# ProPrj_LogicCard.net
KiCad netlist of a schematic drawn in EasyEDA Pro
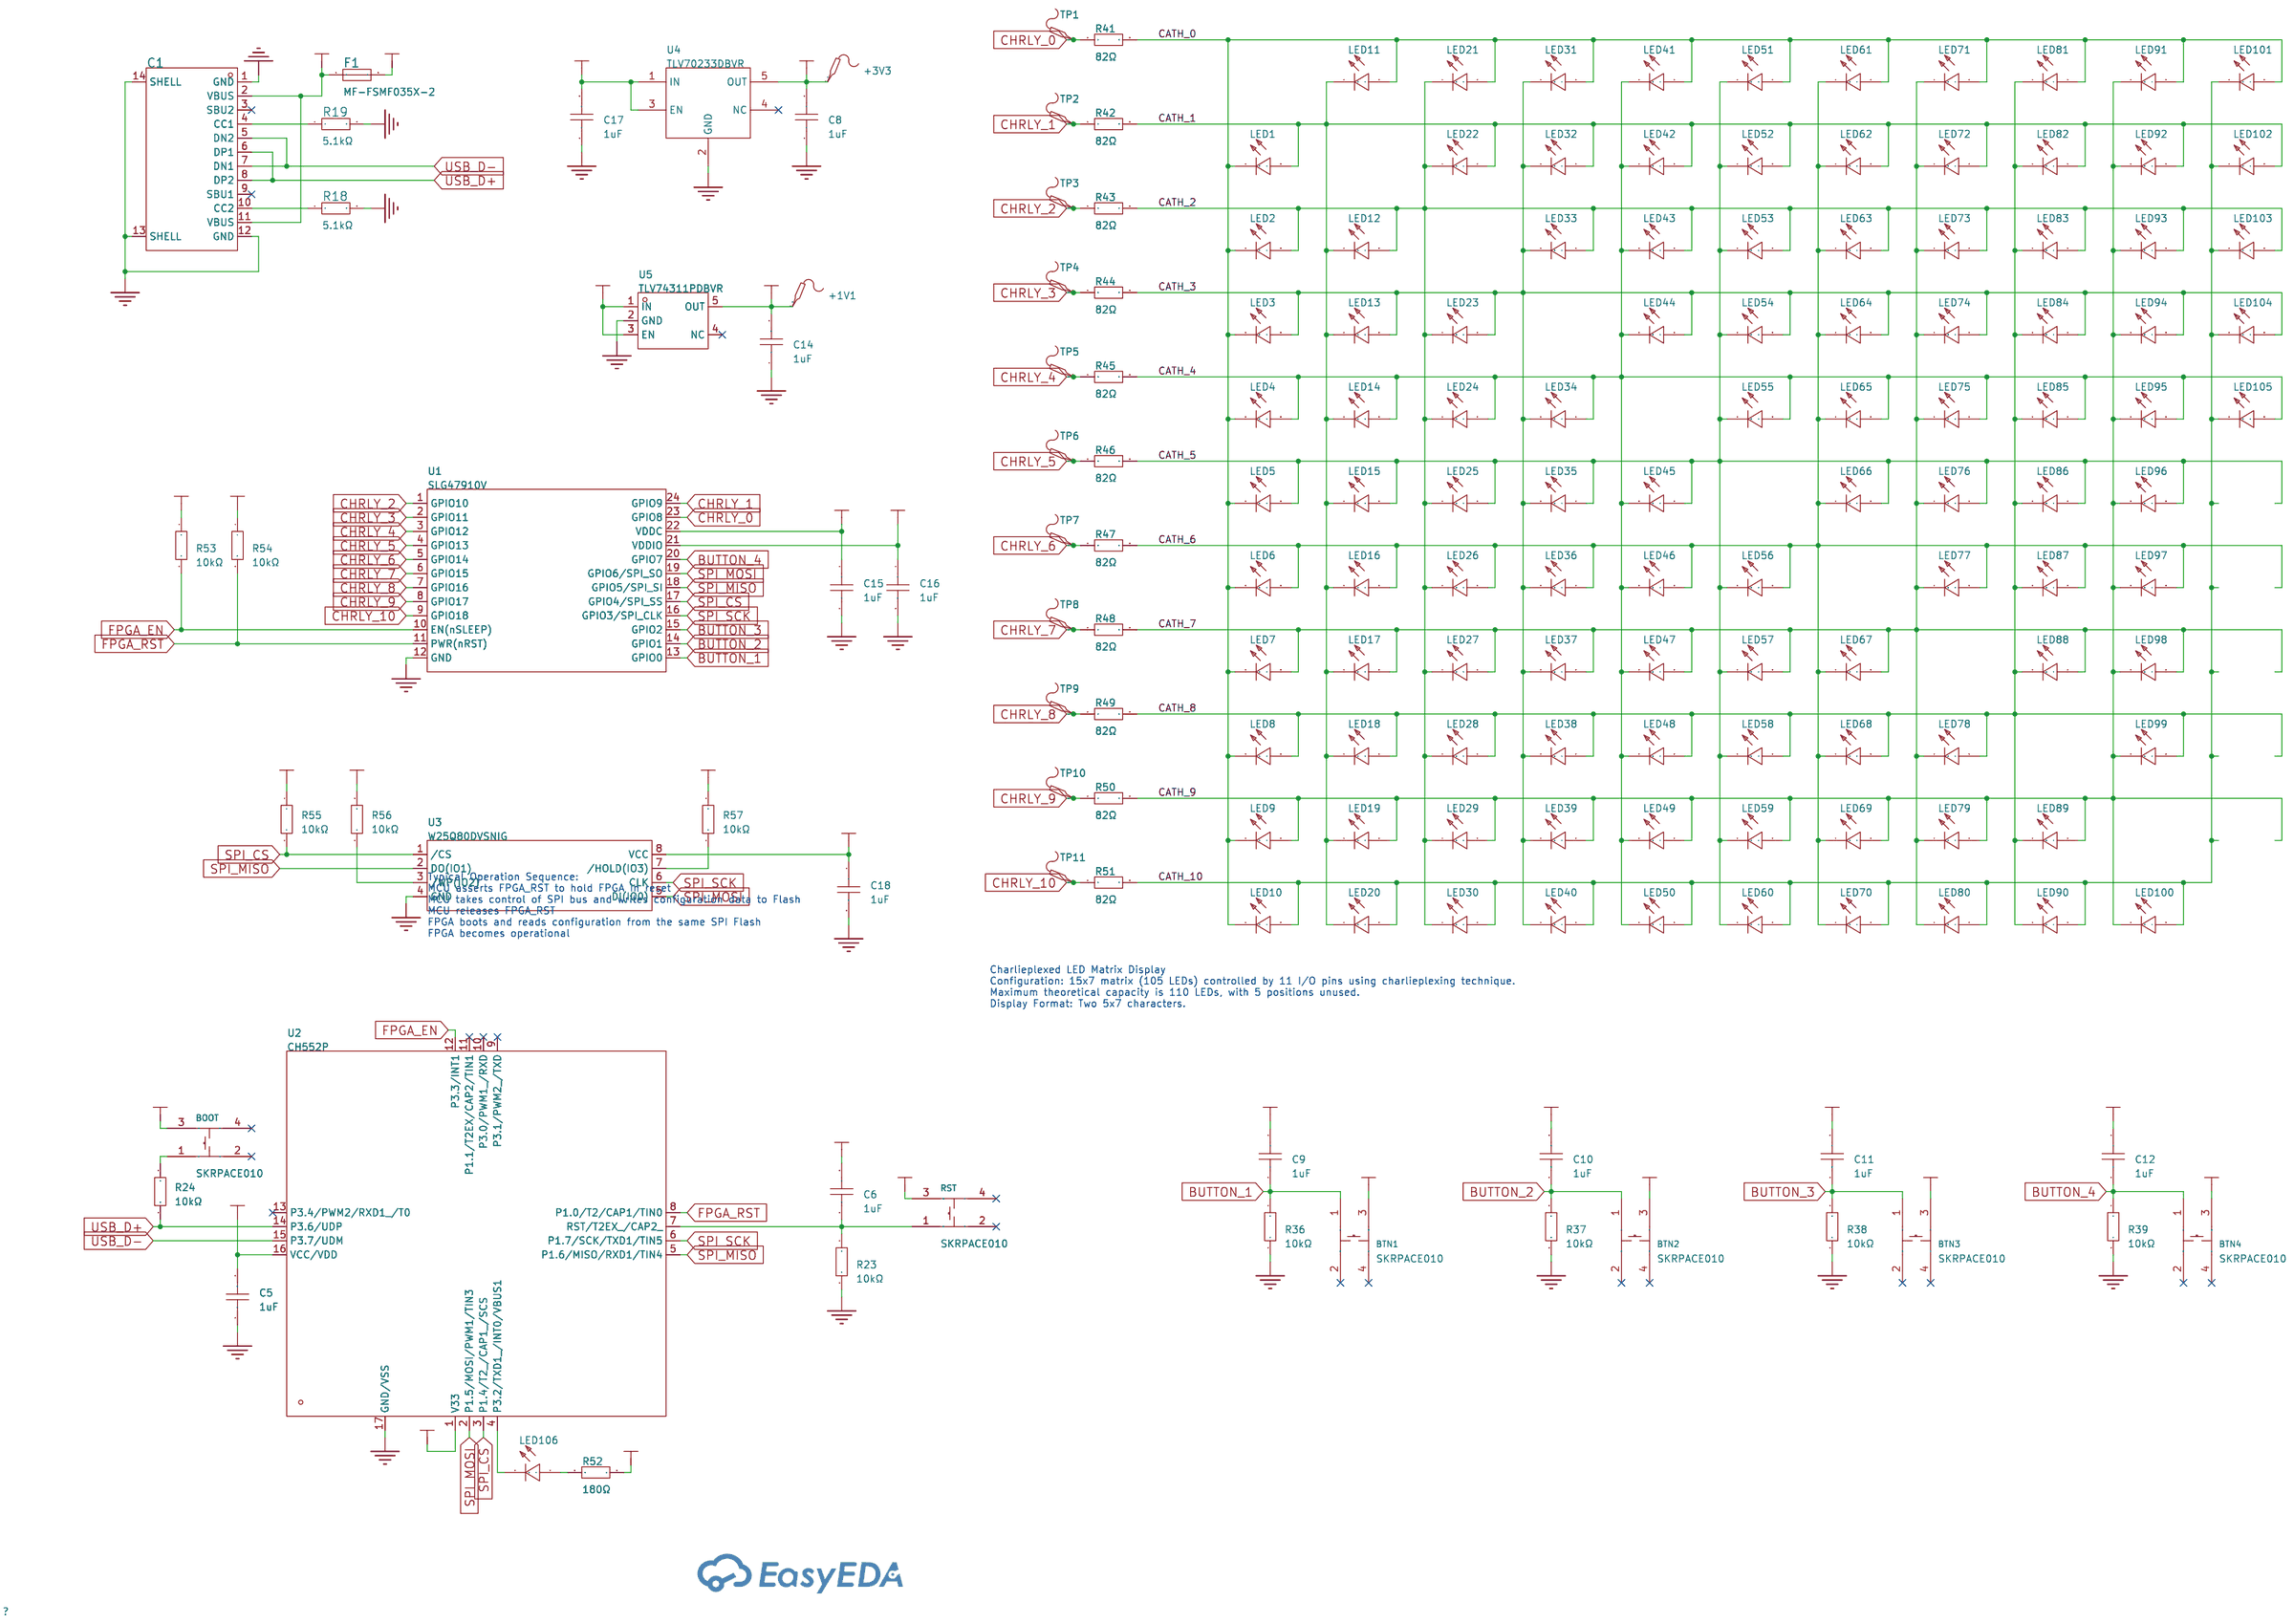
[diagram p0: schematic sheet]

(export (version "E")
  (design (tool "Eeschema 10.0.6"))
  (components
    (comp (ref "+1V1")
      (value "~")
      (footprint "easyedapro:Test-Point-0.5mm")
      (description "Test Point 测试点")
      (libsource (lib "easyedapro") (part "Test-Point"))
    )
    (comp (ref "+3V3")
      (value "~")
      (footprint "easyedapro:Test-Point-0.5mm")
      (description "Test Point 测试点")
      (libsource (lib "easyedapro") (part "Test-Point"))
    )
    (comp (ref "BOOT")
      (value "SKRPACE010")
      (footprint "easyedapro:KEY-SMD_4P-L4.2-W3.2-P2.20-LS4.6")
      (fields (field (name "Manufacturer") "ALPSALPINE(阿尔卑斯阿尔派)"))
      (libsource (lib "easyedapro") (part "SKRPACE010"))
    )
    (comp (ref "BTN1")
      (value "SKRPACE010")
      (footprint "easyedapro:KEY-SMD_4P-L4.2-W3.2-P2.20-LS4.6")
      (fields (field (name "Manufacturer") "ALPSALPINE(阿尔卑斯阿尔派)"))
      (libsource (lib "easyedapro") (part "SKRPACE010"))
    )
    (comp (ref "BTN2")
      (value "SKRPACE010")
      (footprint "easyedapro:KEY-SMD_4P-L4.2-W3.2-P2.20-LS4.6")
      (fields (field (name "Manufacturer") "ALPSALPINE(阿尔卑斯阿尔派)"))
      (libsource (lib "easyedapro") (part "SKRPACE010"))
    )
    (comp (ref "BTN3")
      (value "SKRPACE010")
      (footprint "easyedapro:KEY-SMD_4P-L4.2-W3.2-P2.20-LS4.6")
      (fields (field (name "Manufacturer") "ALPSALPINE(阿尔卑斯阿尔派)"))
      (libsource (lib "easyedapro") (part "SKRPACE010"))
    )
    (comp (ref "BTN4")
      (value "SKRPACE010")
      (footprint "easyedapro:KEY-SMD_4P-L4.2-W3.2-P2.20-LS4.6")
      (fields (field (name "Manufacturer") "ALPSALPINE(阿尔卑斯阿尔派)"))
      (libsource (lib "easyedapro") (part "SKRPACE010"))
    )
    (comp (ref "C1")
      (value "TYPE-C 16PIN 2MD(073)")
      (footprint "easyedapro:USB-C-SMD_TYPE-C-6PIN-2MD-073")
      (fields (field (name "Manufacturer") "SHOU HAN(首韩)"))
      (libsource (lib "easyedapro") (part "TYPE-C 16PIN 2MD(073)"))
    )
    (comp (ref "C5")
      (value "1uF")
      (footprint "easyedapro:C0402")
      (fields
        (field (name "Manufacturer Part") "GRM155Z71A105KE01D")
        (field (name "Manufacturer") "muRata(村田)")
      )
      (libsource (lib "easyedapro") (part "GRM155Z71A105KE01D"))
    )
    (comp (ref "C6")
      (value "1uF")
      (footprint "easyedapro:C0402")
      (fields
        (field (name "Manufacturer Part") "GRM155Z71A105KE01D")
        (field (name "Manufacturer") "muRata(村田)")
      )
      (libsource (lib "easyedapro") (part "GRM155Z71A105KE01D"))
    )
    (comp (ref "C8")
      (value "1uF")
      (footprint "easyedapro:C0402")
      (fields
        (field (name "Manufacturer Part") "GRM155Z71A105KE01D")
        (field (name "Manufacturer") "muRata(村田)")
      )
      (libsource (lib "easyedapro") (part "GRM155Z71A105KE01D"))
    )
    (comp (ref "C9")
      (value "1uF")
      (footprint "easyedapro:C0402")
      (fields
        (field (name "Manufacturer Part") "GRM155Z71A105KE01D")
        (field (name "Manufacturer") "muRata(村田)")
      )
      (libsource (lib "easyedapro") (part "GRM155Z71A105KE01D"))
    )
    (comp (ref "C10")
      (value "1uF")
      (footprint "easyedapro:C0402")
      (fields
        (field (name "Manufacturer Part") "GRM155Z71A105KE01D")
        (field (name "Manufacturer") "muRata(村田)")
      )
      (libsource (lib "easyedapro") (part "GRM155Z71A105KE01D"))
    )
    (comp (ref "C11")
      (value "1uF")
      (footprint "easyedapro:C0402")
      (fields
        (field (name "Manufacturer Part") "GRM155Z71A105KE01D")
        (field (name "Manufacturer") "muRata(村田)")
      )
      (libsource (lib "easyedapro") (part "GRM155Z71A105KE01D"))
    )
    (comp (ref "C12")
      (value "1uF")
      (footprint "easyedapro:C0402")
      (fields
        (field (name "Manufacturer Part") "GRM155Z71A105KE01D")
        (field (name "Manufacturer") "muRata(村田)")
      )
      (libsource (lib "easyedapro") (part "GRM155Z71A105KE01D"))
    )
    (comp (ref "C14")
      (value "1uF")
      (footprint "easyedapro:C0402")
      (fields
        (field (name "Manufacturer Part") "GRM155Z71A105KE01D")
        (field (name "Manufacturer") "muRata(村田)")
      )
      (libsource (lib "easyedapro") (part "GRM155Z71A105KE01D"))
    )
    (comp (ref "C15")
      (value "1uF")
      (footprint "easyedapro:C0402")
      (fields
        (field (name "Manufacturer Part") "GRM155Z71A105KE01D")
        (field (name "Manufacturer") "muRata(村田)")
      )
      (libsource (lib "easyedapro") (part "GRM155Z71A105KE01D"))
    )
    (comp (ref "C16")
      (value "1uF")
      (footprint "easyedapro:C0402")
      (fields
        (field (name "Manufacturer Part") "GRM155Z71A105KE01D")
        (field (name "Manufacturer") "muRata(村田)")
      )
      (libsource (lib "easyedapro") (part "GRM155Z71A105KE01D"))
    )
    (comp (ref "C17")
      (value "1uF")
      (footprint "easyedapro:C0402")
      (fields
        (field (name "Manufacturer Part") "GRM155Z71A105KE01D")
        (field (name "Manufacturer") "muRata(村田)")
      )
      (libsource (lib "easyedapro") (part "GRM155Z71A105KE01D"))
    )
    (comp (ref "C18")
      (value "1uF")
      (footprint "easyedapro:C0402")
      (fields
        (field (name "Manufacturer Part") "GRM155Z71A105KE01D")
        (field (name "Manufacturer") "muRata(村田)")
      )
      (libsource (lib "easyedapro") (part "GRM155Z71A105KE01D"))
    )
    (comp (ref "F1")
      (value "MF-FSMF035X-2")
      (footprint "easyedapro:F0603")
      (fields (field (name "Manufacturer") "BOURNS"))
      (libsource (lib "easyedapro") (part "MF-FSMF035X-2"))
    )
    (comp (ref "LED1")
      (value "19-213/Y2C-CQ2R2L/3T(CY)")
      (footprint "easyedapro:LED0603-RD-YELLOW")
      (fields (field (name "Manufacturer") "EVERLIGHT(亿光)"))
      (libsource (lib "easyedapro") (part "19-213/Y2C-CQ2R2L/3T(CY)"))
    )
    (comp (ref "LED2")
      (value "19-213/Y2C-CQ2R2L/3T(CY)")
      (footprint "easyedapro:LED0603-RD-YELLOW")
      (fields (field (name "Manufacturer") "EVERLIGHT(亿光)"))
      (libsource (lib "easyedapro") (part "19-213/Y2C-CQ2R2L/3T(CY)"))
    )
    (comp (ref "LED3")
      (value "19-213/Y2C-CQ2R2L/3T(CY)")
      (footprint "easyedapro:LED0603-RD-YELLOW")
      (fields (field (name "Manufacturer") "EVERLIGHT(亿光)"))
      (libsource (lib "easyedapro") (part "19-213/Y2C-CQ2R2L/3T(CY)"))
    )
    (comp (ref "LED4")
      (value "19-213/Y2C-CQ2R2L/3T(CY)")
      (footprint "easyedapro:LED0603-RD-YELLOW")
      (fields (field (name "Manufacturer") "EVERLIGHT(亿光)"))
      (libsource (lib "easyedapro") (part "19-213/Y2C-CQ2R2L/3T(CY)"))
    )
    (comp (ref "LED5")
      (value "19-213/Y2C-CQ2R2L/3T(CY)")
      (footprint "easyedapro:LED0603-RD-YELLOW")
      (fields (field (name "Manufacturer") "EVERLIGHT(亿光)"))
      (libsource (lib "easyedapro") (part "19-213/Y2C-CQ2R2L/3T(CY)"))
    )
    (comp (ref "LED6")
      (value "19-213/Y2C-CQ2R2L/3T(CY)")
      (footprint "easyedapro:LED0603-RD-YELLOW")
      (fields (field (name "Manufacturer") "EVERLIGHT(亿光)"))
      (libsource (lib "easyedapro") (part "19-213/Y2C-CQ2R2L/3T(CY)"))
    )
    (comp (ref "LED7")
      (value "19-213/Y2C-CQ2R2L/3T(CY)")
      (footprint "easyedapro:LED0603-RD-YELLOW")
      (fields (field (name "Manufacturer") "EVERLIGHT(亿光)"))
      (libsource (lib "easyedapro") (part "19-213/Y2C-CQ2R2L/3T(CY)"))
    )
    (comp (ref "LED8")
      (value "19-213/Y2C-CQ2R2L/3T(CY)")
      (footprint "easyedapro:LED0603-RD-YELLOW")
      (fields (field (name "Manufacturer") "EVERLIGHT(亿光)"))
      (libsource (lib "easyedapro") (part "19-213/Y2C-CQ2R2L/3T(CY)"))
    )
    (comp (ref "LED9")
      (value "19-213/Y2C-CQ2R2L/3T(CY)")
      (footprint "easyedapro:LED0603-RD-YELLOW")
      (fields (field (name "Manufacturer") "EVERLIGHT(亿光)"))
      (libsource (lib "easyedapro") (part "19-213/Y2C-CQ2R2L/3T(CY)"))
    )
    (comp (ref "LED10")
      (value "19-213/Y2C-CQ2R2L/3T(CY)")
      (footprint "easyedapro:LED0603-RD-YELLOW")
      (fields (field (name "Manufacturer") "EVERLIGHT(亿光)"))
      (libsource (lib "easyedapro") (part "19-213/Y2C-CQ2R2L/3T(CY)"))
    )
    (comp (ref "LED11")
      (value "19-213/Y2C-CQ2R2L/3T(CY)")
      (footprint "easyedapro:LED0603-RD-YELLOW")
      (fields (field (name "Manufacturer") "EVERLIGHT(亿光)"))
      (libsource (lib "easyedapro") (part "19-213/Y2C-CQ2R2L/3T(CY)"))
    )
    (comp (ref "LED12")
      (value "19-213/Y2C-CQ2R2L/3T(CY)")
      (footprint "easyedapro:LED0603-RD-YELLOW")
      (fields (field (name "Manufacturer") "EVERLIGHT(亿光)"))
      (libsource (lib "easyedapro") (part "19-213/Y2C-CQ2R2L/3T(CY)"))
    )
    (comp (ref "LED13")
      (value "19-213/Y2C-CQ2R2L/3T(CY)")
      (footprint "easyedapro:LED0603-RD-YELLOW")
      (fields (field (name "Manufacturer") "EVERLIGHT(亿光)"))
      (libsource (lib "easyedapro") (part "19-213/Y2C-CQ2R2L/3T(CY)"))
    )
    (comp (ref "LED14")
      (value "19-213/Y2C-CQ2R2L/3T(CY)")
      (footprint "easyedapro:LED0603-RD-YELLOW")
      (fields (field (name "Manufacturer") "EVERLIGHT(亿光)"))
      (libsource (lib "easyedapro") (part "19-213/Y2C-CQ2R2L/3T(CY)"))
    )
    (comp (ref "LED15")
      (value "19-213/Y2C-CQ2R2L/3T(CY)")
      (footprint "easyedapro:LED0603-RD-YELLOW")
      (fields (field (name "Manufacturer") "EVERLIGHT(亿光)"))
      (libsource (lib "easyedapro") (part "19-213/Y2C-CQ2R2L/3T(CY)"))
    )
    (comp (ref "LED16")
      (value "19-213/Y2C-CQ2R2L/3T(CY)")
      (footprint "easyedapro:LED0603-RD-YELLOW")
      (fields (field (name "Manufacturer") "EVERLIGHT(亿光)"))
      (libsource (lib "easyedapro") (part "19-213/Y2C-CQ2R2L/3T(CY)"))
    )
    (comp (ref "LED17")
      (value "19-213/Y2C-CQ2R2L/3T(CY)")
      (footprint "easyedapro:LED0603-RD-YELLOW")
      (fields (field (name "Manufacturer") "EVERLIGHT(亿光)"))
      (libsource (lib "easyedapro") (part "19-213/Y2C-CQ2R2L/3T(CY)"))
    )
    (comp (ref "LED18")
      (value "19-213/Y2C-CQ2R2L/3T(CY)")
      (footprint "easyedapro:LED0603-RD-YELLOW")
      (fields (field (name "Manufacturer") "EVERLIGHT(亿光)"))
      (libsource (lib "easyedapro") (part "19-213/Y2C-CQ2R2L/3T(CY)"))
    )
    (comp (ref "LED19")
      (value "19-213/Y2C-CQ2R2L/3T(CY)")
      (footprint "easyedapro:LED0603-RD-YELLOW")
      (fields (field (name "Manufacturer") "EVERLIGHT(亿光)"))
      (libsource (lib "easyedapro") (part "19-213/Y2C-CQ2R2L/3T(CY)"))
    )
    (comp (ref "LED20")
      (value "19-213/Y2C-CQ2R2L/3T(CY)")
      (footprint "easyedapro:LED0603-RD-YELLOW")
      (fields (field (name "Manufacturer") "EVERLIGHT(亿光)"))
      (libsource (lib "easyedapro") (part "19-213/Y2C-CQ2R2L/3T(CY)"))
    )
    (comp (ref "LED21")
      (value "19-213/Y2C-CQ2R2L/3T(CY)")
      (footprint "easyedapro:LED0603-RD-YELLOW")
      (fields (field (name "Manufacturer") "EVERLIGHT(亿光)"))
      (libsource (lib "easyedapro") (part "19-213/Y2C-CQ2R2L/3T(CY)"))
    )
    (comp (ref "LED22")
      (value "19-213/Y2C-CQ2R2L/3T(CY)")
      (footprint "easyedapro:LED0603-RD-YELLOW")
      (fields (field (name "Manufacturer") "EVERLIGHT(亿光)"))
      (libsource (lib "easyedapro") (part "19-213/Y2C-CQ2R2L/3T(CY)"))
    )
    (comp (ref "LED23")
      (value "19-213/Y2C-CQ2R2L/3T(CY)")
      (footprint "easyedapro:LED0603-RD-YELLOW")
      (fields (field (name "Manufacturer") "EVERLIGHT(亿光)"))
      (libsource (lib "easyedapro") (part "19-213/Y2C-CQ2R2L/3T(CY)"))
    )
    (comp (ref "LED24")
      (value "19-213/Y2C-CQ2R2L/3T(CY)")
      (footprint "easyedapro:LED0603-RD-YELLOW")
      (fields (field (name "Manufacturer") "EVERLIGHT(亿光)"))
      (libsource (lib "easyedapro") (part "19-213/Y2C-CQ2R2L/3T(CY)"))
    )
    (comp (ref "LED25")
      (value "19-213/Y2C-CQ2R2L/3T(CY)")
      (footprint "easyedapro:LED0603-RD-YELLOW")
      (fields (field (name "Manufacturer") "EVERLIGHT(亿光)"))
      (libsource (lib "easyedapro") (part "19-213/Y2C-CQ2R2L/3T(CY)"))
    )
    (comp (ref "LED26")
      (value "19-213/Y2C-CQ2R2L/3T(CY)")
      (footprint "easyedapro:LED0603-RD-YELLOW")
      (fields (field (name "Manufacturer") "EVERLIGHT(亿光)"))
      (libsource (lib "easyedapro") (part "19-213/Y2C-CQ2R2L/3T(CY)"))
    )
    (comp (ref "LED27")
      (value "19-213/Y2C-CQ2R2L/3T(CY)")
      (footprint "easyedapro:LED0603-RD-YELLOW")
      (fields (field (name "Manufacturer") "EVERLIGHT(亿光)"))
      (libsource (lib "easyedapro") (part "19-213/Y2C-CQ2R2L/3T(CY)"))
    )
    (comp (ref "LED28")
      (value "19-213/Y2C-CQ2R2L/3T(CY)")
      (footprint "easyedapro:LED0603-RD-YELLOW")
      (fields (field (name "Manufacturer") "EVERLIGHT(亿光)"))
      (libsource (lib "easyedapro") (part "19-213/Y2C-CQ2R2L/3T(CY)"))
    )
    (comp (ref "LED29")
      (value "19-213/Y2C-CQ2R2L/3T(CY)")
      (footprint "easyedapro:LED0603-RD-YELLOW")
      (fields (field (name "Manufacturer") "EVERLIGHT(亿光)"))
      (libsource (lib "easyedapro") (part "19-213/Y2C-CQ2R2L/3T(CY)"))
    )
    (comp (ref "LED30")
      (value "19-213/Y2C-CQ2R2L/3T(CY)")
      (footprint "easyedapro:LED0603-RD-YELLOW")
      (fields (field (name "Manufacturer") "EVERLIGHT(亿光)"))
      (libsource (lib "easyedapro") (part "19-213/Y2C-CQ2R2L/3T(CY)"))
    )
    (comp (ref "LED31")
      (value "19-213/Y2C-CQ2R2L/3T(CY)")
      (footprint "easyedapro:LED0603-RD-YELLOW")
      (fields (field (name "Manufacturer") "EVERLIGHT(亿光)"))
      (libsource (lib "easyedapro") (part "19-213/Y2C-CQ2R2L/3T(CY)"))
    )
    (comp (ref "LED32")
      (value "19-213/Y2C-CQ2R2L/3T(CY)")
      (footprint "easyedapro:LED0603-RD-YELLOW")
      (fields (field (name "Manufacturer") "EVERLIGHT(亿光)"))
      (libsource (lib "easyedapro") (part "19-213/Y2C-CQ2R2L/3T(CY)"))
    )
    (comp (ref "LED33")
      (value "19-213/Y2C-CQ2R2L/3T(CY)")
      (footprint "easyedapro:LED0603-RD-YELLOW")
      (fields (field (name "Manufacturer") "EVERLIGHT(亿光)"))
      (libsource (lib "easyedapro") (part "19-213/Y2C-CQ2R2L/3T(CY)"))
    )
    (comp (ref "LED34")
      (value "19-213/Y2C-CQ2R2L/3T(CY)")
      (footprint "easyedapro:LED0603-RD-YELLOW")
      (fields (field (name "Manufacturer") "EVERLIGHT(亿光)"))
      (libsource (lib "easyedapro") (part "19-213/Y2C-CQ2R2L/3T(CY)"))
    )
    (comp (ref "LED35")
      (value "19-213/Y2C-CQ2R2L/3T(CY)")
      (footprint "easyedapro:LED0603-RD-YELLOW")
      (fields (field (name "Manufacturer") "EVERLIGHT(亿光)"))
      (libsource (lib "easyedapro") (part "19-213/Y2C-CQ2R2L/3T(CY)"))
    )
    (comp (ref "LED36")
      (value "19-213/Y2C-CQ2R2L/3T(CY)")
      (footprint "easyedapro:LED0603-RD-YELLOW")
      (fields (field (name "Manufacturer") "EVERLIGHT(亿光)"))
      (libsource (lib "easyedapro") (part "19-213/Y2C-CQ2R2L/3T(CY)"))
    )
    (comp (ref "LED37")
      (value "19-213/Y2C-CQ2R2L/3T(CY)")
      (footprint "easyedapro:LED0603-RD-YELLOW")
      (fields (field (name "Manufacturer") "EVERLIGHT(亿光)"))
      (libsource (lib "easyedapro") (part "19-213/Y2C-CQ2R2L/3T(CY)"))
    )
    (comp (ref "LED38")
      (value "19-213/Y2C-CQ2R2L/3T(CY)")
      (footprint "easyedapro:LED0603-RD-YELLOW")
      (fields (field (name "Manufacturer") "EVERLIGHT(亿光)"))
      (libsource (lib "easyedapro") (part "19-213/Y2C-CQ2R2L/3T(CY)"))
    )
    (comp (ref "LED39")
      (value "19-213/Y2C-CQ2R2L/3T(CY)")
      (footprint "easyedapro:LED0603-RD-YELLOW")
      (fields (field (name "Manufacturer") "EVERLIGHT(亿光)"))
      (libsource (lib "easyedapro") (part "19-213/Y2C-CQ2R2L/3T(CY)"))
    )
    (comp (ref "LED40")
      (value "19-213/Y2C-CQ2R2L/3T(CY)")
      (footprint "easyedapro:LED0603-RD-YELLOW")
      (fields (field (name "Manufacturer") "EVERLIGHT(亿光)"))
      (libsource (lib "easyedapro") (part "19-213/Y2C-CQ2R2L/3T(CY)"))
    )
    (comp (ref "LED41")
      (value "19-213/Y2C-CQ2R2L/3T(CY)")
      (footprint "easyedapro:LED0603-RD-YELLOW")
      (fields (field (name "Manufacturer") "EVERLIGHT(亿光)"))
      (libsource (lib "easyedapro") (part "19-213/Y2C-CQ2R2L/3T(CY)"))
    )
    (comp (ref "LED42")
      (value "19-213/Y2C-CQ2R2L/3T(CY)")
      (footprint "easyedapro:LED0603-RD-YELLOW")
      (fields (field (name "Manufacturer") "EVERLIGHT(亿光)"))
      (libsource (lib "easyedapro") (part "19-213/Y2C-CQ2R2L/3T(CY)"))
    )
    (comp (ref "LED43")
      (value "19-213/Y2C-CQ2R2L/3T(CY)")
      (footprint "easyedapro:LED0603-RD-YELLOW")
      (fields (field (name "Manufacturer") "EVERLIGHT(亿光)"))
      (libsource (lib "easyedapro") (part "19-213/Y2C-CQ2R2L/3T(CY)"))
    )
    (comp (ref "LED44")
      (value "19-213/Y2C-CQ2R2L/3T(CY)")
      (footprint "easyedapro:LED0603-RD-YELLOW")
      (fields (field (name "Manufacturer") "EVERLIGHT(亿光)"))
      (libsource (lib "easyedapro") (part "19-213/Y2C-CQ2R2L/3T(CY)"))
    )
    (comp (ref "LED45")
      (value "19-213/Y2C-CQ2R2L/3T(CY)")
      (footprint "easyedapro:LED0603-RD-YELLOW")
      (fields (field (name "Manufacturer") "EVERLIGHT(亿光)"))
      (libsource (lib "easyedapro") (part "19-213/Y2C-CQ2R2L/3T(CY)"))
    )
    (comp (ref "LED46")
      (value "19-213/Y2C-CQ2R2L/3T(CY)")
      (footprint "easyedapro:LED0603-RD-YELLOW")
      (fields (field (name "Manufacturer") "EVERLIGHT(亿光)"))
      (libsource (lib "easyedapro") (part "19-213/Y2C-CQ2R2L/3T(CY)"))
    )
    (comp (ref "LED47")
      (value "19-213/Y2C-CQ2R2L/3T(CY)")
      (footprint "easyedapro:LED0603-RD-YELLOW")
      (fields (field (name "Manufacturer") "EVERLIGHT(亿光)"))
      (libsource (lib "easyedapro") (part "19-213/Y2C-CQ2R2L/3T(CY)"))
    )
    (comp (ref "LED48")
      (value "19-213/Y2C-CQ2R2L/3T(CY)")
      (footprint "easyedapro:LED0603-RD-YELLOW")
      (fields (field (name "Manufacturer") "EVERLIGHT(亿光)"))
      (libsource (lib "easyedapro") (part "19-213/Y2C-CQ2R2L/3T(CY)"))
    )
    (comp (ref "LED49")
      (value "19-213/Y2C-CQ2R2L/3T(CY)")
      (footprint "easyedapro:LED0603-RD-YELLOW")
      (fields (field (name "Manufacturer") "EVERLIGHT(亿光)"))
      (libsource (lib "easyedapro") (part "19-213/Y2C-CQ2R2L/3T(CY)"))
    )
    (comp (ref "LED50")
      (value "19-213/Y2C-CQ2R2L/3T(CY)")
      (footprint "easyedapro:LED0603-RD-YELLOW")
      (fields (field (name "Manufacturer") "EVERLIGHT(亿光)"))
      (libsource (lib "easyedapro") (part "19-213/Y2C-CQ2R2L/3T(CY)"))
    )
    (comp (ref "LED51")
      (value "19-213/Y2C-CQ2R2L/3T(CY)")
      (footprint "easyedapro:LED0603-RD-YELLOW")
      (fields (field (name "Manufacturer") "EVERLIGHT(亿光)"))
      (libsource (lib "easyedapro") (part "19-213/Y2C-CQ2R2L/3T(CY)"))
    )
    (comp (ref "LED52")
      (value "19-213/Y2C-CQ2R2L/3T(CY)")
      (footprint "easyedapro:LED0603-RD-YELLOW")
      (fields (field (name "Manufacturer") "EVERLIGHT(亿光)"))
      (libsource (lib "easyedapro") (part "19-213/Y2C-CQ2R2L/3T(CY)"))
    )
    (comp (ref "LED53")
      (value "19-213/Y2C-CQ2R2L/3T(CY)")
      (footprint "easyedapro:LED0603-RD-YELLOW")
      (fields (field (name "Manufacturer") "EVERLIGHT(亿光)"))
      (libsource (lib "easyedapro") (part "19-213/Y2C-CQ2R2L/3T(CY)"))
    )
    (comp (ref "LED54")
      (value "19-213/Y2C-CQ2R2L/3T(CY)")
      (footprint "easyedapro:LED0603-RD-YELLOW")
      (fields (field (name "Manufacturer") "EVERLIGHT(亿光)"))
      (libsource (lib "easyedapro") (part "19-213/Y2C-CQ2R2L/3T(CY)"))
    )
    (comp (ref "LED55")
      (value "19-213/Y2C-CQ2R2L/3T(CY)")
      (footprint "easyedapro:LED0603-RD-YELLOW")
      (fields (field (name "Manufacturer") "EVERLIGHT(亿光)"))
      (libsource (lib "easyedapro") (part "19-213/Y2C-CQ2R2L/3T(CY)"))
    )
    (comp (ref "LED56")
      (value "19-213/Y2C-CQ2R2L/3T(CY)")
      (footprint "easyedapro:LED0603-RD-YELLOW")
      (fields (field (name "Manufacturer") "EVERLIGHT(亿光)"))
      (libsource (lib "easyedapro") (part "19-213/Y2C-CQ2R2L/3T(CY)"))
    )
    (comp (ref "LED57")
      (value "19-213/Y2C-CQ2R2L/3T(CY)")
      (footprint "easyedapro:LED0603-RD-YELLOW")
      (fields (field (name "Manufacturer") "EVERLIGHT(亿光)"))
      (libsource (lib "easyedapro") (part "19-213/Y2C-CQ2R2L/3T(CY)"))
    )
    (comp (ref "LED58")
      (value "19-213/Y2C-CQ2R2L/3T(CY)")
      (footprint "easyedapro:LED0603-RD-YELLOW")
      (fields (field (name "Manufacturer") "EVERLIGHT(亿光)"))
      (libsource (lib "easyedapro") (part "19-213/Y2C-CQ2R2L/3T(CY)"))
    )
    (comp (ref "LED59")
      (value "19-213/Y2C-CQ2R2L/3T(CY)")
      (footprint "easyedapro:LED0603-RD-YELLOW")
      (fields (field (name "Manufacturer") "EVERLIGHT(亿光)"))
      (libsource (lib "easyedapro") (part "19-213/Y2C-CQ2R2L/3T(CY)"))
    )
    (comp (ref "LED60")
      (value "19-213/Y2C-CQ2R2L/3T(CY)")
      (footprint "easyedapro:LED0603-RD-YELLOW")
      (fields (field (name "Manufacturer") "EVERLIGHT(亿光)"))
      (libsource (lib "easyedapro") (part "19-213/Y2C-CQ2R2L/3T(CY)"))
    )
    (comp (ref "LED61")
      (value "19-213/Y2C-CQ2R2L/3T(CY)")
      (footprint "easyedapro:LED0603-RD-YELLOW")
      (fields (field (name "Manufacturer") "EVERLIGHT(亿光)"))
      (libsource (lib "easyedapro") (part "19-213/Y2C-CQ2R2L/3T(CY)"))
    )
    (comp (ref "LED62")
      (value "19-213/Y2C-CQ2R2L/3T(CY)")
      (footprint "easyedapro:LED0603-RD-YELLOW")
      (fields (field (name "Manufacturer") "EVERLIGHT(亿光)"))
      (libsource (lib "easyedapro") (part "19-213/Y2C-CQ2R2L/3T(CY)"))
    )
    (comp (ref "LED63")
      (value "19-213/Y2C-CQ2R2L/3T(CY)")
      (footprint "easyedapro:LED0603-RD-YELLOW")
      (fields (field (name "Manufacturer") "EVERLIGHT(亿光)"))
      (libsource (lib "easyedapro") (part "19-213/Y2C-CQ2R2L/3T(CY)"))
    )
    (comp (ref "LED64")
      (value "19-213/Y2C-CQ2R2L/3T(CY)")
      (footprint "easyedapro:LED0603-RD-YELLOW")
      (fields (field (name "Manufacturer") "EVERLIGHT(亿光)"))
      (libsource (lib "easyedapro") (part "19-213/Y2C-CQ2R2L/3T(CY)"))
    )
    (comp (ref "LED65")
      (value "19-213/Y2C-CQ2R2L/3T(CY)")
      (footprint "easyedapro:LED0603-RD-YELLOW")
      (fields (field (name "Manufacturer") "EVERLIGHT(亿光)"))
      (libsource (lib "easyedapro") (part "19-213/Y2C-CQ2R2L/3T(CY)"))
    )
    (comp (ref "LED66")
      (value "19-213/Y2C-CQ2R2L/3T(CY)")
      (footprint "easyedapro:LED0603-RD-YELLOW")
      (fields (field (name "Manufacturer") "EVERLIGHT(亿光)"))
      (libsource (lib "easyedapro") (part "19-213/Y2C-CQ2R2L/3T(CY)"))
    )
    (comp (ref "LED67")
      (value "19-213/Y2C-CQ2R2L/3T(CY)")
      (footprint "easyedapro:LED0603-RD-YELLOW")
      (fields (field (name "Manufacturer") "EVERLIGHT(亿光)"))
      (libsource (lib "easyedapro") (part "19-213/Y2C-CQ2R2L/3T(CY)"))
    )
    (comp (ref "LED68")
      (value "19-213/Y2C-CQ2R2L/3T(CY)")
      (footprint "easyedapro:LED0603-RD-YELLOW")
      (fields (field (name "Manufacturer") "EVERLIGHT(亿光)"))
      (libsource (lib "easyedapro") (part "19-213/Y2C-CQ2R2L/3T(CY)"))
    )
    (comp (ref "LED69")
      (value "19-213/Y2C-CQ2R2L/3T(CY)")
      (footprint "easyedapro:LED0603-RD-YELLOW")
      (fields (field (name "Manufacturer") "EVERLIGHT(亿光)"))
      (libsource (lib "easyedapro") (part "19-213/Y2C-CQ2R2L/3T(CY)"))
    )
    (comp (ref "LED70")
      (value "19-213/Y2C-CQ2R2L/3T(CY)")
      (footprint "easyedapro:LED0603-RD-YELLOW")
      (fields (field (name "Manufacturer") "EVERLIGHT(亿光)"))
      (libsource (lib "easyedapro") (part "19-213/Y2C-CQ2R2L/3T(CY)"))
    )
    (comp (ref "LED71")
      (value "19-213/Y2C-CQ2R2L/3T(CY)")
      (footprint "easyedapro:LED0603-RD-YELLOW")
      (fields (field (name "Manufacturer") "EVERLIGHT(亿光)"))
      (libsource (lib "easyedapro") (part "19-213/Y2C-CQ2R2L/3T(CY)"))
    )
    (comp (ref "LED72")
      (value "19-213/Y2C-CQ2R2L/3T(CY)")
      (footprint "easyedapro:LED0603-RD-YELLOW")
      (fields (field (name "Manufacturer") "EVERLIGHT(亿光)"))
      (libsource (lib "easyedapro") (part "19-213/Y2C-CQ2R2L/3T(CY)"))
    )
    (comp (ref "LED73")
      (value "19-213/Y2C-CQ2R2L/3T(CY)")
      (footprint "easyedapro:LED0603-RD-YELLOW")
      (fields (field (name "Manufacturer") "EVERLIGHT(亿光)"))
      (libsource (lib "easyedapro") (part "19-213/Y2C-CQ2R2L/3T(CY)"))
    )
    (comp (ref "LED74")
      (value "19-213/Y2C-CQ2R2L/3T(CY)")
      (footprint "easyedapro:LED0603-RD-YELLOW")
      (fields (field (name "Manufacturer") "EVERLIGHT(亿光)"))
      (libsource (lib "easyedapro") (part "19-213/Y2C-CQ2R2L/3T(CY)"))
    )
    (comp (ref "LED75")
      (value "19-213/Y2C-CQ2R2L/3T(CY)")
      (footprint "easyedapro:LED0603-RD-YELLOW")
      (fields (field (name "Manufacturer") "EVERLIGHT(亿光)"))
      (libsource (lib "easyedapro") (part "19-213/Y2C-CQ2R2L/3T(CY)"))
    )
    (comp (ref "LED76")
      (value "19-213/Y2C-CQ2R2L/3T(CY)")
      (footprint "easyedapro:LED0603-RD-YELLOW")
      (fields (field (name "Manufacturer") "EVERLIGHT(亿光)"))
      (libsource (lib "easyedapro") (part "19-213/Y2C-CQ2R2L/3T(CY)"))
    )
    (comp (ref "LED77")
      (value "19-213/Y2C-CQ2R2L/3T(CY)")
      (footprint "easyedapro:LED0603-RD-YELLOW")
      (fields (field (name "Manufacturer") "EVERLIGHT(亿光)"))
      (libsource (lib "easyedapro") (part "19-213/Y2C-CQ2R2L/3T(CY)"))
    )
    (comp (ref "LED78")
      (value "19-213/Y2C-CQ2R2L/3T(CY)")
      (footprint "easyedapro:LED0603-RD-YELLOW")
      (fields (field (name "Manufacturer") "EVERLIGHT(亿光)"))
      (libsource (lib "easyedapro") (part "19-213/Y2C-CQ2R2L/3T(CY)"))
    )
    (comp (ref "LED79")
      (value "19-213/Y2C-CQ2R2L/3T(CY)")
      (footprint "easyedapro:LED0603-RD-YELLOW")
      (fields (field (name "Manufacturer") "EVERLIGHT(亿光)"))
      (libsource (lib "easyedapro") (part "19-213/Y2C-CQ2R2L/3T(CY)"))
    )
    (comp (ref "LED80")
      (value "19-213/Y2C-CQ2R2L/3T(CY)")
      (footprint "easyedapro:LED0603-RD-YELLOW")
      (fields (field (name "Manufacturer") "EVERLIGHT(亿光)"))
      (libsource (lib "easyedapro") (part "19-213/Y2C-CQ2R2L/3T(CY)"))
    )
    (comp (ref "LED81")
      (value "19-213/Y2C-CQ2R2L/3T(CY)")
      (footprint "easyedapro:LED0603-RD-YELLOW")
      (fields (field (name "Manufacturer") "EVERLIGHT(亿光)"))
      (libsource (lib "easyedapro") (part "19-213/Y2C-CQ2R2L/3T(CY)"))
    )
    (comp (ref "LED82")
      (value "19-213/Y2C-CQ2R2L/3T(CY)")
      (footprint "easyedapro:LED0603-RD-YELLOW")
      (fields (field (name "Manufacturer") "EVERLIGHT(亿光)"))
      (libsource (lib "easyedapro") (part "19-213/Y2C-CQ2R2L/3T(CY)"))
    )
    (comp (ref "LED83")
      (value "19-213/Y2C-CQ2R2L/3T(CY)")
      (footprint "easyedapro:LED0603-RD-YELLOW")
      (fields (field (name "Manufacturer") "EVERLIGHT(亿光)"))
      (libsource (lib "easyedapro") (part "19-213/Y2C-CQ2R2L/3T(CY)"))
    )
    (comp (ref "LED84")
      (value "19-213/Y2C-CQ2R2L/3T(CY)")
      (footprint "easyedapro:LED0603-RD-YELLOW")
      (fields (field (name "Manufacturer") "EVERLIGHT(亿光)"))
      (libsource (lib "easyedapro") (part "19-213/Y2C-CQ2R2L/3T(CY)"))
    )
    (comp (ref "LED85")
      (value "19-213/Y2C-CQ2R2L/3T(CY)")
      (footprint "easyedapro:LED0603-RD-YELLOW")
      (fields (field (name "Manufacturer") "EVERLIGHT(亿光)"))
      (libsource (lib "easyedapro") (part "19-213/Y2C-CQ2R2L/3T(CY)"))
    )
    (comp (ref "LED86")
      (value "19-213/Y2C-CQ2R2L/3T(CY)")
      (footprint "easyedapro:LED0603-RD-YELLOW")
      (fields (field (name "Manufacturer") "EVERLIGHT(亿光)"))
      (libsource (lib "easyedapro") (part "19-213/Y2C-CQ2R2L/3T(CY)"))
    )
    (comp (ref "LED87")
      (value "19-213/Y2C-CQ2R2L/3T(CY)")
      (footprint "easyedapro:LED0603-RD-YELLOW")
      (fields (field (name "Manufacturer") "EVERLIGHT(亿光)"))
      (libsource (lib "easyedapro") (part "19-213/Y2C-CQ2R2L/3T(CY)"))
    )
    (comp (ref "LED88")
      (value "19-213/Y2C-CQ2R2L/3T(CY)")
      (footprint "easyedapro:LED0603-RD-YELLOW")
      (fields (field (name "Manufacturer") "EVERLIGHT(亿光)"))
      (libsource (lib "easyedapro") (part "19-213/Y2C-CQ2R2L/3T(CY)"))
    )
    (comp (ref "LED89")
      (value "19-213/Y2C-CQ2R2L/3T(CY)")
      (footprint "easyedapro:LED0603-RD-YELLOW")
      (fields (field (name "Manufacturer") "EVERLIGHT(亿光)"))
      (libsource (lib "easyedapro") (part "19-213/Y2C-CQ2R2L/3T(CY)"))
    )
    (comp (ref "LED90")
      (value "19-213/Y2C-CQ2R2L/3T(CY)")
      (footprint "easyedapro:LED0603-RD-YELLOW")
      (fields (field (name "Manufacturer") "EVERLIGHT(亿光)"))
      (libsource (lib "easyedapro") (part "19-213/Y2C-CQ2R2L/3T(CY)"))
    )
    (comp (ref "LED91")
      (value "19-213/Y2C-CQ2R2L/3T(CY)")
      (footprint "easyedapro:LED0603-RD-YELLOW")
      (fields (field (name "Manufacturer") "EVERLIGHT(亿光)"))
      (libsource (lib "easyedapro") (part "19-213/Y2C-CQ2R2L/3T(CY)"))
    )
    (comp (ref "LED92")
      (value "19-213/Y2C-CQ2R2L/3T(CY)")
      (footprint "easyedapro:LED0603-RD-YELLOW")
      (fields (field (name "Manufacturer") "EVERLIGHT(亿光)"))
      (libsource (lib "easyedapro") (part "19-213/Y2C-CQ2R2L/3T(CY)"))
    )
    (comp (ref "LED93")
      (value "19-213/Y2C-CQ2R2L/3T(CY)")
      (footprint "easyedapro:LED0603-RD-YELLOW")
      (fields (field (name "Manufacturer") "EVERLIGHT(亿光)"))
      (libsource (lib "easyedapro") (part "19-213/Y2C-CQ2R2L/3T(CY)"))
    )
    (comp (ref "LED94")
      (value "19-213/Y2C-CQ2R2L/3T(CY)")
      (footprint "easyedapro:LED0603-RD-YELLOW")
      (fields (field (name "Manufacturer") "EVERLIGHT(亿光)"))
      (libsource (lib "easyedapro") (part "19-213/Y2C-CQ2R2L/3T(CY)"))
    )
    (comp (ref "LED95")
      (value "19-213/Y2C-CQ2R2L/3T(CY)")
      (footprint "easyedapro:LED0603-RD-YELLOW")
      (fields (field (name "Manufacturer") "EVERLIGHT(亿光)"))
      (libsource (lib "easyedapro") (part "19-213/Y2C-CQ2R2L/3T(CY)"))
    )
    (comp (ref "LED96")
      (value "19-213/Y2C-CQ2R2L/3T(CY)")
      (footprint "easyedapro:LED0603-RD-YELLOW")
      (fields (field (name "Manufacturer") "EVERLIGHT(亿光)"))
      (libsource (lib "easyedapro") (part "19-213/Y2C-CQ2R2L/3T(CY)"))
    )
    (comp (ref "LED97")
      (value "19-213/Y2C-CQ2R2L/3T(CY)")
      (footprint "easyedapro:LED0603-RD-YELLOW")
      (fields (field (name "Manufacturer") "EVERLIGHT(亿光)"))
      (libsource (lib "easyedapro") (part "19-213/Y2C-CQ2R2L/3T(CY)"))
    )
    (comp (ref "LED98")
      (value "19-213/Y2C-CQ2R2L/3T(CY)")
      (footprint "easyedapro:LED0603-RD-YELLOW")
      (fields (field (name "Manufacturer") "EVERLIGHT(亿光)"))
      (libsource (lib "easyedapro") (part "19-213/Y2C-CQ2R2L/3T(CY)"))
    )
    (comp (ref "LED99")
      (value "19-213/Y2C-CQ2R2L/3T(CY)")
      (footprint "easyedapro:LED0603-RD-YELLOW")
      (fields (field (name "Manufacturer") "EVERLIGHT(亿光)"))
      (libsource (lib "easyedapro") (part "19-213/Y2C-CQ2R2L/3T(CY)"))
    )
    (comp (ref "LED100")
      (value "19-213/Y2C-CQ2R2L/3T(CY)")
      (footprint "easyedapro:LED0603-RD-YELLOW")
      (fields (field (name "Manufacturer") "EVERLIGHT(亿光)"))
      (libsource (lib "easyedapro") (part "19-213/Y2C-CQ2R2L/3T(CY)"))
    )
    (comp (ref "LED101")
      (value "19-213/Y2C-CQ2R2L/3T(CY)")
      (footprint "easyedapro:LED0603-RD-YELLOW")
      (fields (field (name "Manufacturer") "EVERLIGHT(亿光)"))
      (libsource (lib "easyedapro") (part "19-213/Y2C-CQ2R2L/3T(CY)"))
    )
    (comp (ref "LED102")
      (value "19-213/Y2C-CQ2R2L/3T(CY)")
      (footprint "easyedapro:LED0603-RD-YELLOW")
      (fields (field (name "Manufacturer") "EVERLIGHT(亿光)"))
      (libsource (lib "easyedapro") (part "19-213/Y2C-CQ2R2L/3T(CY)"))
    )
    (comp (ref "LED103")
      (value "19-213/Y2C-CQ2R2L/3T(CY)")
      (footprint "easyedapro:LED0603-RD-YELLOW")
      (fields (field (name "Manufacturer") "EVERLIGHT(亿光)"))
      (libsource (lib "easyedapro") (part "19-213/Y2C-CQ2R2L/3T(CY)"))
    )
    (comp (ref "LED104")
      (value "19-213/Y2C-CQ2R2L/3T(CY)")
      (footprint "easyedapro:LED0603-RD-YELLOW")
      (fields (field (name "Manufacturer") "EVERLIGHT(亿光)"))
      (libsource (lib "easyedapro") (part "19-213/Y2C-CQ2R2L/3T(CY)"))
    )
    (comp (ref "LED105")
      (value "19-213/Y2C-CQ2R2L/3T(CY)")
      (footprint "easyedapro:LED0603-RD-YELLOW")
      (fields (field (name "Manufacturer") "EVERLIGHT(亿光)"))
      (libsource (lib "easyedapro") (part "19-213/Y2C-CQ2R2L/3T(CY)"))
    )
    (comp (ref "LED106")
      (value "19-213/Y2C-CQ2R2L/3T(CY)")
      (footprint "easyedapro:LED0603-RD-YELLOW")
      (fields (field (name "Manufacturer") "EVERLIGHT(亿光)"))
      (libsource (lib "easyedapro") (part "19-213/Y2C-CQ2R2L/3T(CY)"))
    )
    (comp (ref "R18")
      (value "5.1kΩ")
      (footprint "easyedapro:R0402")
      (fields (field (name "Manufacturer Part") "RC0402JR-075K1L") (field (name "Manufacturer") "YAGEO(国巨)"))
      (libsource (lib "easyedapro") (part "RC0402JR-075K1L"))
    )
    (comp (ref "R19")
      (value "5.1kΩ")
      (footprint "easyedapro:R0402")
      (fields (field (name "Manufacturer Part") "RC0402JR-075K1L") (field (name "Manufacturer") "YAGEO(国巨)"))
      (libsource (lib "easyedapro") (part "RC0402JR-075K1L"))
    )
    (comp (ref "R23")
      (value "10kΩ")
      (footprint "easyedapro:R0402")
      (fields (field (name "Manufacturer Part") "RC0402FR-0710KL") (field (name "Manufacturer") "YAGEO(国巨)"))
      (libsource (lib "easyedapro") (part "RC0402FR-0710KL"))
    )
    (comp (ref "R24")
      (value "10kΩ")
      (footprint "easyedapro:R0402")
      (fields (field (name "Manufacturer Part") "RC0402FR-0710KL") (field (name "Manufacturer") "YAGEO(国巨)"))
      (libsource (lib "easyedapro") (part "RC0402FR-0710KL"))
    )
    (comp (ref "R36")
      (value "10kΩ")
      (footprint "easyedapro:R0402")
      (fields (field (name "Manufacturer Part") "RC0402FR-0710KL") (field (name "Manufacturer") "YAGEO(国巨)"))
      (libsource (lib "easyedapro") (part "RC0402FR-0710KL"))
    )
    (comp (ref "R37")
      (value "10kΩ")
      (footprint "easyedapro:R0402")
      (fields (field (name "Manufacturer Part") "RC0402FR-0710KL") (field (name "Manufacturer") "YAGEO(国巨)"))
      (libsource (lib "easyedapro") (part "RC0402FR-0710KL"))
    )
    (comp (ref "R38")
      (value "10kΩ")
      (footprint "easyedapro:R0402")
      (fields (field (name "Manufacturer Part") "RC0402FR-0710KL") (field (name "Manufacturer") "YAGEO(国巨)"))
      (libsource (lib "easyedapro") (part "RC0402FR-0710KL"))
    )
    (comp (ref "R39")
      (value "10kΩ")
      (footprint "easyedapro:R0402")
      (fields (field (name "Manufacturer Part") "RC0402FR-0710KL") (field (name "Manufacturer") "YAGEO(国巨)"))
      (libsource (lib "easyedapro") (part "RC0402FR-0710KL"))
    )
    (comp (ref "R41")
      (value "82Ω")
      (footprint "easyedapro:R0402")
      (fields (field (name "Manufacturer Part") "RC0402FR-0782RL") (field (name "Manufacturer") "YAGEO(国巨)"))
      (libsource (lib "easyedapro") (part "RC0402FR-0782RL"))
    )
    (comp (ref "R42")
      (value "82Ω")
      (footprint "easyedapro:R0402")
      (fields (field (name "Manufacturer Part") "RC0402FR-0782RL") (field (name "Manufacturer") "YAGEO(国巨)"))
      (libsource (lib "easyedapro") (part "RC0402FR-0782RL"))
    )
    (comp (ref "R43")
      (value "82Ω")
      (footprint "easyedapro:R0402")
      (fields (field (name "Manufacturer Part") "RC0402FR-0782RL") (field (name "Manufacturer") "YAGEO(国巨)"))
      (libsource (lib "easyedapro") (part "RC0402FR-0782RL"))
    )
    (comp (ref "R44")
      (value "82Ω")
      (footprint "easyedapro:R0402")
      (fields (field (name "Manufacturer Part") "RC0402FR-0782RL") (field (name "Manufacturer") "YAGEO(国巨)"))
      (libsource (lib "easyedapro") (part "RC0402FR-0782RL"))
    )
    (comp (ref "R45")
      (value "82Ω")
      (footprint "easyedapro:R0402")
      (fields (field (name "Manufacturer Part") "RC0402FR-0782RL") (field (name "Manufacturer") "YAGEO(国巨)"))
      (libsource (lib "easyedapro") (part "RC0402FR-0782RL"))
    )
    (comp (ref "R46")
      (value "82Ω")
      (footprint "easyedapro:R0402")
      (fields (field (name "Manufacturer Part") "RC0402FR-0782RL") (field (name "Manufacturer") "YAGEO(国巨)"))
      (libsource (lib "easyedapro") (part "RC0402FR-0782RL"))
    )
    (comp (ref "R47")
      (value "82Ω")
      (footprint "easyedapro:R0402")
      (fields (field (name "Manufacturer Part") "RC0402FR-0782RL") (field (name "Manufacturer") "YAGEO(国巨)"))
      (libsource (lib "easyedapro") (part "RC0402FR-0782RL"))
    )
    (comp (ref "R48")
      (value "82Ω")
      (footprint "easyedapro:R0402")
      (fields (field (name "Manufacturer Part") "RC0402FR-0782RL") (field (name "Manufacturer") "YAGEO(国巨)"))
      (libsource (lib "easyedapro") (part "RC0402FR-0782RL"))
    )
    (comp (ref "R49")
      (value "82Ω")
      (footprint "easyedapro:R0402")
      (fields (field (name "Manufacturer Part") "RC0402FR-0782RL") (field (name "Manufacturer") "YAGEO(国巨)"))
      (libsource (lib "easyedapro") (part "RC0402FR-0782RL"))
    )
    (comp (ref "R50")
      (value "82Ω")
      (footprint "easyedapro:R0402")
      (fields (field (name "Manufacturer Part") "RC0402FR-0782RL") (field (name "Manufacturer") "YAGEO(国巨)"))
      (libsource (lib "easyedapro") (part "RC0402FR-0782RL"))
    )
    (comp (ref "R51")
      (value "82Ω")
      (footprint "easyedapro:R0402")
      (fields (field (name "Manufacturer Part") "RC0402FR-0782RL") (field (name "Manufacturer") "YAGEO(国巨)"))
      (libsource (lib "easyedapro") (part "RC0402FR-0782RL"))
    )
    (comp (ref "R52")
      (value "180Ω")
      (footprint "easyedapro:R0402")
      (fields (field (name "Manufacturer Part") "RC0402FR-07180RL") (field (name "Manufacturer") "YAGEO(国巨)"))
      (libsource (lib "easyedapro") (part "RC0402FR-07180RL"))
    )
    (comp (ref "R53")
      (value "10kΩ")
      (footprint "easyedapro:R0402")
      (fields (field (name "Manufacturer Part") "RC0402FR-0710KL") (field (name "Manufacturer") "YAGEO(国巨)"))
      (libsource (lib "easyedapro") (part "RC0402FR-0710KL"))
    )
    (comp (ref "R54")
      (value "10kΩ")
      (footprint "easyedapro:R0402")
      (fields (field (name "Manufacturer Part") "RC0402FR-0710KL") (field (name "Manufacturer") "YAGEO(国巨)"))
      (libsource (lib "easyedapro") (part "RC0402FR-0710KL"))
    )
    (comp (ref "R55")
      (value "10kΩ")
      (footprint "easyedapro:R0402")
      (fields (field (name "Manufacturer Part") "RC0402FR-0710KL") (field (name "Manufacturer") "YAGEO(国巨)"))
      (libsource (lib "easyedapro") (part "RC0402FR-0710KL"))
    )
    (comp (ref "R56")
      (value "10kΩ")
      (footprint "easyedapro:R0402")
      (fields (field (name "Manufacturer Part") "RC0402FR-0710KL") (field (name "Manufacturer") "YAGEO(国巨)"))
      (libsource (lib "easyedapro") (part "RC0402FR-0710KL"))
    )
    (comp (ref "R57")
      (value "10kΩ")
      (footprint "easyedapro:R0402")
      (fields (field (name "Manufacturer Part") "RC0402FR-0710KL") (field (name "Manufacturer") "YAGEO(国巨)"))
      (libsource (lib "easyedapro") (part "RC0402FR-0710KL"))
    )
    (comp (ref "RST")
      (value "SKRPACE010")
      (footprint "easyedapro:KEY-SMD_4P-L4.2-W3.2-P2.20-LS4.6")
      (fields (field (name "Manufacturer") "ALPSALPINE(阿尔卑斯阿尔派)"))
      (libsource (lib "easyedapro") (part "SKRPACE010"))
    )
    (comp (ref "TP1")
      (value "~")
      (footprint "easyedapro:Test-Point-0.5mm")
      (description "Test Point 测试点")
      (libsource (lib "easyedapro") (part "Test-Point"))
    )
    (comp (ref "TP2")
      (value "~")
      (footprint "easyedapro:Test-Point-0.5mm")
      (description "Test Point 测试点")
      (libsource (lib "easyedapro") (part "Test-Point"))
    )
    (comp (ref "TP3")
      (value "~")
      (footprint "easyedapro:Test-Point-0.5mm")
      (description "Test Point 测试点")
      (libsource (lib "easyedapro") (part "Test-Point"))
    )
    (comp (ref "TP4")
      (value "~")
      (footprint "easyedapro:Test-Point-0.5mm")
      (description "Test Point 测试点")
      (libsource (lib "easyedapro") (part "Test-Point"))
    )
    (comp (ref "TP5")
      (value "~")
      (footprint "easyedapro:Test-Point-0.5mm")
      (description "Test Point 测试点")
      (libsource (lib "easyedapro") (part "Test-Point"))
    )
    (comp (ref "TP6")
      (value "~")
      (footprint "easyedapro:Test-Point-0.5mm")
      (description "Test Point 测试点")
      (libsource (lib "easyedapro") (part "Test-Point"))
    )
    (comp (ref "TP7")
      (value "~")
      (footprint "easyedapro:Test-Point-0.5mm")
      (description "Test Point 测试点")
      (libsource (lib "easyedapro") (part "Test-Point"))
    )
    (comp (ref "TP8")
      (value "~")
      (footprint "easyedapro:Test-Point-0.5mm")
      (description "Test Point 测试点")
      (libsource (lib "easyedapro") (part "Test-Point"))
    )
    (comp (ref "TP9")
      (value "~")
      (footprint "easyedapro:Test-Point-0.5mm")
      (description "Test Point 测试点")
      (libsource (lib "easyedapro") (part "Test-Point"))
    )
    (comp (ref "TP10")
      (value "~")
      (footprint "easyedapro:Test-Point-0.5mm")
      (description "Test Point 测试点")
      (libsource (lib "easyedapro") (part "Test-Point"))
    )
    (comp (ref "TP11")
      (value "~")
      (footprint "easyedapro:Test-Point-0.5mm")
      (description "Test Point 测试点")
      (libsource (lib "easyedapro") (part "Test-Point"))
    )
    (comp (ref "U1")
      (value "SLG47910V")
      (footprint "easyedapro:STQFN-24_L3.0-W3.0-P0.4_SLG47910V")
      (libsource (lib "easyedapro") (part "SLG47910V"))
    )
    (comp (ref "U2")
      (value "CH552P")
      (footprint "easyedapro:VQFN-16_L3.0-W3.0-P0.50-BL-EP1.7")
      (fields (field (name "Manufacturer") "WCH(南京沁恒)"))
      (libsource (lib "easyedapro") (part "CH552P"))
    )
    (comp (ref "U3")
      (value "W25Q80DVSNIG")
      (footprint "easyedapro:SOIC-8_L4.9-W3.9-P1.27-LS6.0-BL")
      (fields (field (name "Manufacturer") "Winbond(华邦)"))
      (libsource (lib "easyedapro") (part "W25Q80DVSNIG"))
    )
    (comp (ref "U4")
      (value "TLV70233DBVR")
      (footprint "easyedapro:SOT-23-5_L3.0-W1.7-P0.95-LS2.8-BR")
      (fields (field (name "Manufacturer") "TI(德州仪器)"))
      (libsource (lib "easyedapro") (part "TLV70233DBVR"))
    )
    (comp (ref "U5")
      (value "TLV74311PDBVR")
      (footprint "easyedapro:SOT-23-5_L3.0-W1.7-P0.95-LS2.8-BL")
      (fields (field (name "Manufacturer") "TI(德州仪器)"))
      (libsource (lib "easyedapro") (part "TLV74311PDBVR"))
    )
  )
  (nets
    (net (code "1") (name "+1V1") (class "Default")
      (node (ref "+1V1") (pin "1") (pinfunction "1_1") (pintype "unspecified"))
      (node (ref "C14") (pin "2") (pinfunction "2_2") (pintype "unspecified"))
      (node (ref "C15") (pin "1") (pinfunction "1_1") (pintype "unspecified"))
      (node (ref "U1") (pin "22") (pinfunction "VDDC_22") (pintype "unspecified"))
      (node (ref "U5") (pin "5") (pinfunction "OUT_5") (pintype "unspecified"))
    )
    (net (code "2") (name "+3V3") (class "Default")
      (node (ref "+3V3") (pin "1") (pinfunction "1_1") (pintype "unspecified"))
      (node (ref "BOOT") (pin "3") (pinfunction "3_3") (pintype "input"))
      (node (ref "BTN1") (pin "3") (pinfunction "3_3") (pintype "input"))
      (node (ref "BTN2") (pin "3") (pinfunction "3_3") (pintype "input"))
      (node (ref "BTN3") (pin "3") (pinfunction "3_3") (pintype "input"))
      (node (ref "BTN4") (pin "3") (pinfunction "3_3") (pintype "input"))
      (node (ref "C10") (pin "2") (pinfunction "2_2") (pintype "unspecified"))
      (node (ref "C11") (pin "2") (pinfunction "2_2") (pintype "unspecified"))
      (node (ref "C12") (pin "2") (pinfunction "2_2") (pintype "unspecified"))
      (node (ref "C16") (pin "1") (pinfunction "1_1") (pintype "unspecified"))
      (node (ref "C18") (pin "1") (pinfunction "1_1") (pintype "unspecified"))
      (node (ref "C5") (pin "2") (pinfunction "2_2") (pintype "unspecified"))
      (node (ref "C6") (pin "2") (pinfunction "2_2") (pintype "unspecified"))
      (node (ref "C8") (pin "2") (pinfunction "2_2") (pintype "unspecified"))
      (node (ref "C9") (pin "2") (pinfunction "2_2") (pintype "unspecified"))
      (node (ref "R52") (pin "2") (pinfunction "2_2") (pintype "input"))
      (node (ref "R53") (pin "1") (pinfunction "1_1") (pintype "input"))
      (node (ref "R54") (pin "1") (pinfunction "1_1") (pintype "input"))
      (node (ref "R55") (pin "1") (pinfunction "1_1") (pintype "input"))
      (node (ref "R56") (pin "1") (pinfunction "1_1") (pintype "input"))
      (node (ref "R57") (pin "1") (pinfunction "1_1") (pintype "input"))
      (node (ref "RST") (pin "3") (pinfunction "3_3") (pintype "input"))
      (node (ref "U1") (pin "21") (pinfunction "VDDIO_21") (pintype "unspecified"))
      (node (ref "U2") (pin "1") (pinfunction "V33_1") (pintype "unspecified"))
      (node (ref "U2") (pin "16") (pinfunction "VCC/VDD_16") (pintype "unspecified"))
      (node (ref "U3") (pin "8") (pinfunction "VCC_8") (pintype "unspecified"))
      (node (ref "U4") (pin "5") (pinfunction "OUT_5") (pintype "unspecified"))
      (node (ref "U5") (pin "1") (pinfunction "IN_1") (pintype "unspecified"))
      (node (ref "U5") (pin "3") (pinfunction "EN_3") (pintype "unspecified"))
    )
    (net (code "3") (name "/CATH_0") (class "Default")
      (node (ref "LED1") (pin "1") (pinfunction "C_1") (pintype "input"))
      (node (ref "LED10") (pin "1") (pinfunction "C_1") (pintype "input"))
      (node (ref "LED101") (pin "2") (pinfunction "A_2") (pintype "input"))
      (node (ref "LED11") (pin "2") (pinfunction "A_2") (pintype "input"))
      (node (ref "LED2") (pin "1") (pinfunction "C_1") (pintype "input"))
      (node (ref "LED21") (pin "2") (pinfunction "A_2") (pintype "input"))
      (node (ref "LED3") (pin "1") (pinfunction "C_1") (pintype "input"))
      (node (ref "LED31") (pin "2") (pinfunction "A_2") (pintype "input"))
      (node (ref "LED4") (pin "1") (pinfunction "C_1") (pintype "input"))
      (node (ref "LED41") (pin "2") (pinfunction "A_2") (pintype "input"))
      (node (ref "LED5") (pin "1") (pinfunction "C_1") (pintype "input"))
      (node (ref "LED51") (pin "2") (pinfunction "A_2") (pintype "input"))
      (node (ref "LED6") (pin "1") (pinfunction "C_1") (pintype "input"))
      (node (ref "LED61") (pin "2") (pinfunction "A_2") (pintype "input"))
      (node (ref "LED7") (pin "1") (pinfunction "C_1") (pintype "input"))
      (node (ref "LED71") (pin "2") (pinfunction "A_2") (pintype "input"))
      (node (ref "LED8") (pin "1") (pinfunction "C_1") (pintype "input"))
      (node (ref "LED81") (pin "2") (pinfunction "A_2") (pintype "input"))
      (node (ref "LED9") (pin "1") (pinfunction "C_1") (pintype "input"))
      (node (ref "LED91") (pin "2") (pinfunction "A_2") (pintype "input"))
      (node (ref "R41") (pin "2") (pinfunction "2_2") (pintype "unspecified"))
    )
    (net (code "4") (name "/CATH_1") (class "Default")
      (node (ref "LED1") (pin "2") (pinfunction "A_2") (pintype "input"))
      (node (ref "LED102") (pin "2") (pinfunction "A_2") (pintype "input"))
      (node (ref "LED11") (pin "1") (pinfunction "C_1") (pintype "input"))
      (node (ref "LED12") (pin "1") (pinfunction "C_1") (pintype "input"))
      (node (ref "LED13") (pin "1") (pinfunction "C_1") (pintype "input"))
      (node (ref "LED14") (pin "1") (pinfunction "C_1") (pintype "input"))
      (node (ref "LED15") (pin "1") (pinfunction "C_1") (pintype "input"))
      (node (ref "LED16") (pin "1") (pinfunction "C_1") (pintype "input"))
      (node (ref "LED17") (pin "1") (pinfunction "C_1") (pintype "input"))
      (node (ref "LED18") (pin "1") (pinfunction "C_1") (pintype "input"))
      (node (ref "LED19") (pin "1") (pinfunction "C_1") (pintype "input"))
      (node (ref "LED20") (pin "1") (pinfunction "C_1") (pintype "input"))
      (node (ref "LED22") (pin "2") (pinfunction "A_2") (pintype "input"))
      (node (ref "LED32") (pin "2") (pinfunction "A_2") (pintype "input"))
      (node (ref "LED42") (pin "2") (pinfunction "A_2") (pintype "input"))
      (node (ref "LED52") (pin "2") (pinfunction "A_2") (pintype "input"))
      (node (ref "LED62") (pin "2") (pinfunction "A_2") (pintype "input"))
      (node (ref "LED72") (pin "2") (pinfunction "A_2") (pintype "input"))
      (node (ref "LED82") (pin "2") (pinfunction "A_2") (pintype "input"))
      (node (ref "LED92") (pin "2") (pinfunction "A_2") (pintype "input"))
      (node (ref "R42") (pin "2") (pinfunction "2_2") (pintype "unspecified"))
    )
    (net (code "5") (name "/CATH_2") (class "Default")
      (node (ref "LED103") (pin "2") (pinfunction "A_2") (pintype "input"))
      (node (ref "LED12") (pin "2") (pinfunction "A_2") (pintype "input"))
      (node (ref "LED2") (pin "2") (pinfunction "A_2") (pintype "input"))
      (node (ref "LED21") (pin "1") (pinfunction "C_1") (pintype "input"))
      (node (ref "LED22") (pin "1") (pinfunction "C_1") (pintype "input"))
      (node (ref "LED23") (pin "1") (pinfunction "C_1") (pintype "input"))
      (node (ref "LED24") (pin "1") (pinfunction "C_1") (pintype "input"))
      (node (ref "LED25") (pin "1") (pinfunction "C_1") (pintype "input"))
      (node (ref "LED26") (pin "1") (pinfunction "C_1") (pintype "input"))
      (node (ref "LED27") (pin "1") (pinfunction "C_1") (pintype "input"))
      (node (ref "LED28") (pin "1") (pinfunction "C_1") (pintype "input"))
      (node (ref "LED29") (pin "1") (pinfunction "C_1") (pintype "input"))
      (node (ref "LED30") (pin "1") (pinfunction "C_1") (pintype "input"))
      (node (ref "LED33") (pin "2") (pinfunction "A_2") (pintype "input"))
      (node (ref "LED43") (pin "2") (pinfunction "A_2") (pintype "input"))
      (node (ref "LED53") (pin "2") (pinfunction "A_2") (pintype "input"))
      (node (ref "LED63") (pin "2") (pinfunction "A_2") (pintype "input"))
      (node (ref "LED73") (pin "2") (pinfunction "A_2") (pintype "input"))
      (node (ref "LED83") (pin "2") (pinfunction "A_2") (pintype "input"))
      (node (ref "LED93") (pin "2") (pinfunction "A_2") (pintype "input"))
      (node (ref "R43") (pin "2") (pinfunction "2_2") (pintype "unspecified"))
    )
    (net (code "6") (name "/CATH_3") (class "Default")
      (node (ref "LED104") (pin "2") (pinfunction "A_2") (pintype "input"))
      (node (ref "LED13") (pin "2") (pinfunction "A_2") (pintype "input"))
      (node (ref "LED23") (pin "2") (pinfunction "A_2") (pintype "input"))
      (node (ref "LED3") (pin "2") (pinfunction "A_2") (pintype "input"))
      (node (ref "LED31") (pin "1") (pinfunction "C_1") (pintype "input"))
      (node (ref "LED32") (pin "1") (pinfunction "C_1") (pintype "input"))
      (node (ref "LED33") (pin "1") (pinfunction "C_1") (pintype "input"))
      (node (ref "LED34") (pin "1") (pinfunction "C_1") (pintype "input"))
      (node (ref "LED35") (pin "1") (pinfunction "C_1") (pintype "input"))
      (node (ref "LED36") (pin "1") (pinfunction "C_1") (pintype "input"))
      (node (ref "LED37") (pin "1") (pinfunction "C_1") (pintype "input"))
      (node (ref "LED38") (pin "1") (pinfunction "C_1") (pintype "input"))
      (node (ref "LED39") (pin "1") (pinfunction "C_1") (pintype "input"))
      (node (ref "LED40") (pin "1") (pinfunction "C_1") (pintype "input"))
      (node (ref "LED44") (pin "2") (pinfunction "A_2") (pintype "input"))
      (node (ref "LED54") (pin "2") (pinfunction "A_2") (pintype "input"))
      (node (ref "LED64") (pin "2") (pinfunction "A_2") (pintype "input"))
      (node (ref "LED74") (pin "2") (pinfunction "A_2") (pintype "input"))
      (node (ref "LED84") (pin "2") (pinfunction "A_2") (pintype "input"))
      (node (ref "LED94") (pin "2") (pinfunction "A_2") (pintype "input"))
      (node (ref "R44") (pin "2") (pinfunction "2_2") (pintype "unspecified"))
    )
    (net (code "7") (name "/CATH_4") (class "Default")
      (node (ref "LED105") (pin "2") (pinfunction "A_2") (pintype "input"))
      (node (ref "LED14") (pin "2") (pinfunction "A_2") (pintype "input"))
      (node (ref "LED24") (pin "2") (pinfunction "A_2") (pintype "input"))
      (node (ref "LED34") (pin "2") (pinfunction "A_2") (pintype "input"))
      (node (ref "LED4") (pin "2") (pinfunction "A_2") (pintype "input"))
      (node (ref "LED41") (pin "1") (pinfunction "C_1") (pintype "input"))
      (node (ref "LED42") (pin "1") (pinfunction "C_1") (pintype "input"))
      (node (ref "LED43") (pin "1") (pinfunction "C_1") (pintype "input"))
      (node (ref "LED44") (pin "1") (pinfunction "C_1") (pintype "input"))
      (node (ref "LED45") (pin "1") (pinfunction "C_1") (pintype "input"))
      (node (ref "LED46") (pin "1") (pinfunction "C_1") (pintype "input"))
      (node (ref "LED47") (pin "1") (pinfunction "C_1") (pintype "input"))
      (node (ref "LED48") (pin "1") (pinfunction "C_1") (pintype "input"))
      (node (ref "LED49") (pin "1") (pinfunction "C_1") (pintype "input"))
      (node (ref "LED50") (pin "1") (pinfunction "C_1") (pintype "input"))
      (node (ref "LED55") (pin "2") (pinfunction "A_2") (pintype "input"))
      (node (ref "LED65") (pin "2") (pinfunction "A_2") (pintype "input"))
      (node (ref "LED75") (pin "2") (pinfunction "A_2") (pintype "input"))
      (node (ref "LED85") (pin "2") (pinfunction "A_2") (pintype "input"))
      (node (ref "LED95") (pin "2") (pinfunction "A_2") (pintype "input"))
      (node (ref "R45") (pin "2") (pinfunction "2_2") (pintype "unspecified"))
    )
    (net (code "8") (name "/CATH_5") (class "Default")
      (node (ref "LED15") (pin "2") (pinfunction "A_2") (pintype "input"))
      (node (ref "LED25") (pin "2") (pinfunction "A_2") (pintype "input"))
      (node (ref "LED35") (pin "2") (pinfunction "A_2") (pintype "input"))
      (node (ref "LED45") (pin "2") (pinfunction "A_2") (pintype "input"))
      (node (ref "LED5") (pin "2") (pinfunction "A_2") (pintype "input"))
      (node (ref "LED51") (pin "1") (pinfunction "C_1") (pintype "input"))
      (node (ref "LED52") (pin "1") (pinfunction "C_1") (pintype "input"))
      (node (ref "LED53") (pin "1") (pinfunction "C_1") (pintype "input"))
      (node (ref "LED54") (pin "1") (pinfunction "C_1") (pintype "input"))
      (node (ref "LED55") (pin "1") (pinfunction "C_1") (pintype "input"))
      (node (ref "LED56") (pin "1") (pinfunction "C_1") (pintype "input"))
      (node (ref "LED57") (pin "1") (pinfunction "C_1") (pintype "input"))
      (node (ref "LED58") (pin "1") (pinfunction "C_1") (pintype "input"))
      (node (ref "LED59") (pin "1") (pinfunction "C_1") (pintype "input"))
      (node (ref "LED60") (pin "1") (pinfunction "C_1") (pintype "input"))
      (node (ref "LED66") (pin "2") (pinfunction "A_2") (pintype "input"))
      (node (ref "LED76") (pin "2") (pinfunction "A_2") (pintype "input"))
      (node (ref "LED86") (pin "2") (pinfunction "A_2") (pintype "input"))
      (node (ref "LED96") (pin "2") (pinfunction "A_2") (pintype "input"))
      (node (ref "R46") (pin "2") (pinfunction "2_2") (pintype "unspecified"))
    )
    (net (code "9") (name "/CATH_6") (class "Default")
      (node (ref "LED16") (pin "2") (pinfunction "A_2") (pintype "input"))
      (node (ref "LED26") (pin "2") (pinfunction "A_2") (pintype "input"))
      (node (ref "LED36") (pin "2") (pinfunction "A_2") (pintype "input"))
      (node (ref "LED46") (pin "2") (pinfunction "A_2") (pintype "input"))
      (node (ref "LED56") (pin "2") (pinfunction "A_2") (pintype "input"))
      (node (ref "LED6") (pin "2") (pinfunction "A_2") (pintype "input"))
      (node (ref "LED61") (pin "1") (pinfunction "C_1") (pintype "input"))
      (node (ref "LED62") (pin "1") (pinfunction "C_1") (pintype "input"))
      (node (ref "LED63") (pin "1") (pinfunction "C_1") (pintype "input"))
      (node (ref "LED64") (pin "1") (pinfunction "C_1") (pintype "input"))
      (node (ref "LED65") (pin "1") (pinfunction "C_1") (pintype "input"))
      (node (ref "LED66") (pin "1") (pinfunction "C_1") (pintype "input"))
      (node (ref "LED67") (pin "1") (pinfunction "C_1") (pintype "input"))
      (node (ref "LED68") (pin "1") (pinfunction "C_1") (pintype "input"))
      (node (ref "LED69") (pin "1") (pinfunction "C_1") (pintype "input"))
      (node (ref "LED70") (pin "1") (pinfunction "C_1") (pintype "input"))
      (node (ref "LED77") (pin "2") (pinfunction "A_2") (pintype "input"))
      (node (ref "LED87") (pin "2") (pinfunction "A_2") (pintype "input"))
      (node (ref "LED97") (pin "2") (pinfunction "A_2") (pintype "input"))
      (node (ref "R47") (pin "2") (pinfunction "2_2") (pintype "unspecified"))
    )
    (net (code "10") (name "/CATH_7") (class "Default")
      (node (ref "LED17") (pin "2") (pinfunction "A_2") (pintype "input"))
      (node (ref "LED27") (pin "2") (pinfunction "A_2") (pintype "input"))
      (node (ref "LED37") (pin "2") (pinfunction "A_2") (pintype "input"))
      (node (ref "LED47") (pin "2") (pinfunction "A_2") (pintype "input"))
      (node (ref "LED57") (pin "2") (pinfunction "A_2") (pintype "input"))
      (node (ref "LED67") (pin "2") (pinfunction "A_2") (pintype "input"))
      (node (ref "LED7") (pin "2") (pinfunction "A_2") (pintype "input"))
      (node (ref "LED71") (pin "1") (pinfunction "C_1") (pintype "input"))
      (node (ref "LED72") (pin "1") (pinfunction "C_1") (pintype "input"))
      (node (ref "LED73") (pin "1") (pinfunction "C_1") (pintype "input"))
      (node (ref "LED74") (pin "1") (pinfunction "C_1") (pintype "input"))
      (node (ref "LED75") (pin "1") (pinfunction "C_1") (pintype "input"))
      (node (ref "LED76") (pin "1") (pinfunction "C_1") (pintype "input"))
      (node (ref "LED77") (pin "1") (pinfunction "C_1") (pintype "input"))
      (node (ref "LED78") (pin "1") (pinfunction "C_1") (pintype "input"))
      (node (ref "LED79") (pin "1") (pinfunction "C_1") (pintype "input"))
      (node (ref "LED80") (pin "1") (pinfunction "C_1") (pintype "input"))
      (node (ref "LED88") (pin "2") (pinfunction "A_2") (pintype "input"))
      (node (ref "LED98") (pin "2") (pinfunction "A_2") (pintype "input"))
      (node (ref "R48") (pin "2") (pinfunction "2_2") (pintype "unspecified"))
    )
    (net (code "11") (name "/CATH_8") (class "Default")
      (node (ref "LED18") (pin "2") (pinfunction "A_2") (pintype "input"))
      (node (ref "LED28") (pin "2") (pinfunction "A_2") (pintype "input"))
      (node (ref "LED38") (pin "2") (pinfunction "A_2") (pintype "input"))
      (node (ref "LED48") (pin "2") (pinfunction "A_2") (pintype "input"))
      (node (ref "LED58") (pin "2") (pinfunction "A_2") (pintype "input"))
      (node (ref "LED68") (pin "2") (pinfunction "A_2") (pintype "input"))
      (node (ref "LED78") (pin "2") (pinfunction "A_2") (pintype "input"))
      (node (ref "LED8") (pin "2") (pinfunction "A_2") (pintype "input"))
      (node (ref "LED81") (pin "1") (pinfunction "C_1") (pintype "input"))
      (node (ref "LED82") (pin "1") (pinfunction "C_1") (pintype "input"))
      (node (ref "LED83") (pin "1") (pinfunction "C_1") (pintype "input"))
      (node (ref "LED84") (pin "1") (pinfunction "C_1") (pintype "input"))
      (node (ref "LED85") (pin "1") (pinfunction "C_1") (pintype "input"))
      (node (ref "LED86") (pin "1") (pinfunction "C_1") (pintype "input"))
      (node (ref "LED87") (pin "1") (pinfunction "C_1") (pintype "input"))
      (node (ref "LED88") (pin "1") (pinfunction "C_1") (pintype "input"))
      (node (ref "LED89") (pin "1") (pinfunction "C_1") (pintype "input"))
      (node (ref "LED90") (pin "1") (pinfunction "C_1") (pintype "input"))
      (node (ref "LED99") (pin "2") (pinfunction "A_2") (pintype "input"))
      (node (ref "R49") (pin "2") (pinfunction "2_2") (pintype "unspecified"))
    )
    (net (code "12") (name "/CATH_9") (class "Default")
      (node (ref "LED100") (pin "1") (pinfunction "C_1") (pintype "input"))
      (node (ref "LED19") (pin "2") (pinfunction "A_2") (pintype "input"))
      (node (ref "LED29") (pin "2") (pinfunction "A_2") (pintype "input"))
      (node (ref "LED39") (pin "2") (pinfunction "A_2") (pintype "input"))
      (node (ref "LED49") (pin "2") (pinfunction "A_2") (pintype "input"))
      (node (ref "LED59") (pin "2") (pinfunction "A_2") (pintype "input"))
      (node (ref "LED69") (pin "2") (pinfunction "A_2") (pintype "input"))
      (node (ref "LED79") (pin "2") (pinfunction "A_2") (pintype "input"))
      (node (ref "LED89") (pin "2") (pinfunction "A_2") (pintype "input"))
      (node (ref "LED9") (pin "2") (pinfunction "A_2") (pintype "input"))
      (node (ref "LED91") (pin "1") (pinfunction "C_1") (pintype "input"))
      (node (ref "LED92") (pin "1") (pinfunction "C_1") (pintype "input"))
      (node (ref "LED93") (pin "1") (pinfunction "C_1") (pintype "input"))
      (node (ref "LED94") (pin "1") (pinfunction "C_1") (pintype "input"))
      (node (ref "LED95") (pin "1") (pinfunction "C_1") (pintype "input"))
      (node (ref "LED96") (pin "1") (pinfunction "C_1") (pintype "input"))
      (node (ref "LED97") (pin "1") (pinfunction "C_1") (pintype "input"))
      (node (ref "LED98") (pin "1") (pinfunction "C_1") (pintype "input"))
      (node (ref "LED99") (pin "1") (pinfunction "C_1") (pintype "input"))
      (node (ref "R50") (pin "2") (pinfunction "2_2") (pintype "unspecified"))
    )
    (net (code "13") (name "/CATH_10") (class "Default")
      (node (ref "LED10") (pin "2") (pinfunction "A_2") (pintype "input"))
      (node (ref "LED100") (pin "2") (pinfunction "A_2") (pintype "input"))
      (node (ref "LED101") (pin "1") (pinfunction "C_1") (pintype "input"))
      (node (ref "LED102") (pin "1") (pinfunction "C_1") (pintype "input"))
      (node (ref "LED103") (pin "1") (pinfunction "C_1") (pintype "input"))
      (node (ref "LED104") (pin "1") (pinfunction "C_1") (pintype "input"))
      (node (ref "LED105") (pin "1") (pinfunction "C_1") (pintype "input"))
      (node (ref "LED20") (pin "2") (pinfunction "A_2") (pintype "input"))
      (node (ref "LED30") (pin "2") (pinfunction "A_2") (pintype "input"))
      (node (ref "LED40") (pin "2") (pinfunction "A_2") (pintype "input"))
      (node (ref "LED50") (pin "2") (pinfunction "A_2") (pintype "input"))
      (node (ref "LED60") (pin "2") (pinfunction "A_2") (pintype "input"))
      (node (ref "LED70") (pin "2") (pinfunction "A_2") (pintype "input"))
      (node (ref "LED80") (pin "2") (pinfunction "A_2") (pintype "input"))
      (node (ref "LED90") (pin "2") (pinfunction "A_2") (pintype "input"))
      (node (ref "R51") (pin "2") (pinfunction "2_2") (pintype "unspecified"))
    )
    (net (code "14") (name "BUTTON_1") (class "Default")
      (node (ref "BTN1") (pin "1") (pinfunction "1_1") (pintype "input"))
      (node (ref "C9") (pin "1") (pinfunction "1_1") (pintype "unspecified"))
      (node (ref "R36") (pin "1") (pinfunction "1_1") (pintype "input"))
      (node (ref "U1") (pin "13") (pinfunction "GPIO0_13") (pintype "unspecified"))
    )
    (net (code "15") (name "BUTTON_2") (class "Default")
      (node (ref "BTN2") (pin "1") (pinfunction "1_1") (pintype "input"))
      (node (ref "C10") (pin "1") (pinfunction "1_1") (pintype "unspecified"))
      (node (ref "R37") (pin "1") (pinfunction "1_1") (pintype "input"))
      (node (ref "U1") (pin "14") (pinfunction "GPIO1_14") (pintype "unspecified"))
    )
    (net (code "16") (name "BUTTON_3") (class "Default")
      (node (ref "BTN3") (pin "1") (pinfunction "1_1") (pintype "input"))
      (node (ref "C11") (pin "1") (pinfunction "1_1") (pintype "unspecified"))
      (node (ref "R38") (pin "1") (pinfunction "1_1") (pintype "input"))
      (node (ref "U1") (pin "15") (pinfunction "GPIO2_15") (pintype "unspecified"))
    )
    (net (code "17") (name "BUTTON_4") (class "Default")
      (node (ref "BTN4") (pin "1") (pinfunction "1_1") (pintype "input"))
      (node (ref "C12") (pin "1") (pinfunction "1_1") (pintype "unspecified"))
      (node (ref "R39") (pin "1") (pinfunction "1_1") (pintype "input"))
      (node (ref "U1") (pin "20") (pinfunction "GPIO7_20") (pintype "unspecified"))
    )
    (net (code "18") (name "CHRLY_0") (class "Default")
      (node (ref "R41") (pin "1") (pinfunction "1_1") (pintype "unspecified"))
      (node (ref "TP1") (pin "1") (pinfunction "1_1") (pintype "unspecified"))
      (node (ref "U1") (pin "23") (pinfunction "GPIO8_23") (pintype "unspecified"))
    )
    (net (code "19") (name "CHRLY_1") (class "Default")
      (node (ref "R42") (pin "1") (pinfunction "1_1") (pintype "unspecified"))
      (node (ref "TP2") (pin "1") (pinfunction "1_1") (pintype "unspecified"))
      (node (ref "U1") (pin "24") (pinfunction "GPIO9_24") (pintype "unspecified"))
    )
    (net (code "20") (name "CHRLY_2") (class "Default")
      (node (ref "R43") (pin "1") (pinfunction "1_1") (pintype "unspecified"))
      (node (ref "TP3") (pin "1") (pinfunction "1_1") (pintype "unspecified"))
      (node (ref "U1") (pin "1") (pinfunction "GPIO10_1") (pintype "unspecified"))
    )
    (net (code "21") (name "CHRLY_3") (class "Default")
      (node (ref "R44") (pin "1") (pinfunction "1_1") (pintype "unspecified"))
      (node (ref "TP4") (pin "1") (pinfunction "1_1") (pintype "unspecified"))
      (node (ref "U1") (pin "2") (pinfunction "GPIO11_2") (pintype "unspecified"))
    )
    (net (code "22") (name "CHRLY_4") (class "Default")
      (node (ref "R45") (pin "1") (pinfunction "1_1") (pintype "unspecified"))
      (node (ref "TP5") (pin "1") (pinfunction "1_1") (pintype "unspecified"))
      (node (ref "U1") (pin "3") (pinfunction "GPIO12_3") (pintype "unspecified"))
    )
    (net (code "23") (name "CHRLY_5") (class "Default")
      (node (ref "R46") (pin "1") (pinfunction "1_1") (pintype "unspecified"))
      (node (ref "TP6") (pin "1") (pinfunction "1_1") (pintype "unspecified"))
      (node (ref "U1") (pin "4") (pinfunction "GPIO13_4") (pintype "unspecified"))
    )
    (net (code "24") (name "CHRLY_6") (class "Default")
      (node (ref "R47") (pin "1") (pinfunction "1_1") (pintype "unspecified"))
      (node (ref "TP7") (pin "1") (pinfunction "1_1") (pintype "unspecified"))
      (node (ref "U1") (pin "5") (pinfunction "GPIO14_5") (pintype "unspecified"))
    )
    (net (code "25") (name "CHRLY_7") (class "Default")
      (node (ref "R48") (pin "1") (pinfunction "1_1") (pintype "unspecified"))
      (node (ref "TP8") (pin "1") (pinfunction "1_1") (pintype "unspecified"))
      (node (ref "U1") (pin "6") (pinfunction "GPIO15_6") (pintype "unspecified"))
    )
    (net (code "26") (name "CHRLY_8") (class "Default")
      (node (ref "R49") (pin "1") (pinfunction "1_1") (pintype "unspecified"))
      (node (ref "TP9") (pin "1") (pinfunction "1_1") (pintype "unspecified"))
      (node (ref "U1") (pin "7") (pinfunction "GPIO16_7") (pintype "unspecified"))
    )
    (net (code "27") (name "CHRLY_9") (class "Default")
      (node (ref "R50") (pin "1") (pinfunction "1_1") (pintype "unspecified"))
      (node (ref "TP10") (pin "1") (pinfunction "1_1") (pintype "unspecified"))
      (node (ref "U1") (pin "8") (pinfunction "GPIO17_8") (pintype "unspecified"))
    )
    (net (code "28") (name "CHRLY_10") (class "Default")
      (node (ref "R51") (pin "1") (pinfunction "1_1") (pintype "unspecified"))
      (node (ref "TP11") (pin "1") (pinfunction "1_1") (pintype "unspecified"))
      (node (ref "U1") (pin "9") (pinfunction "GPIO18_9") (pintype "unspecified"))
    )
    (net (code "29") (name "FPGA_EN") (class "Default")
      (node (ref "R53") (pin "2") (pinfunction "2_2") (pintype "input"))
      (node (ref "U1") (pin "10") (pinfunction "EN(nSLEEP)_10") (pintype "unspecified"))
      (node (ref "U2") (pin "12") (pinfunction "P3.3/INT1_12") (pintype "unspecified"))
    )
    (net (code "30") (name "FPGA_RST") (class "Default")
      (node (ref "R54") (pin "2") (pinfunction "2_2") (pintype "input"))
      (node (ref "U1") (pin "11") (pinfunction "PWR(nRST)_11") (pintype "unspecified"))
      (node (ref "U2") (pin "8") (pinfunction "P1.0/T2/CAP1/TIN0_8") (pintype "unspecified"))
    )
    (net (code "31") (name "GND") (class "Default")
      (node (ref "C1") (pin "1") (pinfunction "GND_1") (pintype "unspecified"))
      (node (ref "C1") (pin "12") (pinfunction "GND_12") (pintype "unspecified"))
      (node (ref "C1") (pin "13") (pinfunction "SHELL_13") (pintype "unspecified"))
      (node (ref "C1") (pin "14") (pinfunction "SHELL_14") (pintype "unspecified"))
      (node (ref "C14") (pin "1") (pinfunction "1_1") (pintype "unspecified"))
      (node (ref "C15") (pin "2") (pinfunction "2_2") (pintype "unspecified"))
      (node (ref "C16") (pin "2") (pinfunction "2_2") (pintype "unspecified"))
      (node (ref "C17") (pin "1") (pinfunction "1_1") (pintype "unspecified"))
      (node (ref "C18") (pin "2") (pinfunction "2_2") (pintype "unspecified"))
      (node (ref "C5") (pin "1") (pinfunction "1_1") (pintype "unspecified"))
      (node (ref "C8") (pin "1") (pinfunction "1_1") (pintype "unspecified"))
      (node (ref "R18") (pin "2") (pinfunction "2_2") (pintype "input"))
      (node (ref "R19") (pin "2") (pinfunction "2_2") (pintype "input"))
      (node (ref "R23") (pin "2") (pinfunction "2_2") (pintype "input"))
      (node (ref "R36") (pin "2") (pinfunction "2_2") (pintype "input"))
      (node (ref "R37") (pin "2") (pinfunction "2_2") (pintype "input"))
      (node (ref "R38") (pin "2") (pinfunction "2_2") (pintype "input"))
      (node (ref "R39") (pin "2") (pinfunction "2_2") (pintype "input"))
      (node (ref "U1") (pin "12") (pinfunction "GND_12") (pintype "unspecified"))
      (node (ref "U2") (pin "17") (pinfunction "GND/VSS_17") (pintype "unspecified"))
      (node (ref "U3") (pin "4") (pinfunction "GND_4") (pintype "unspecified"))
      (node (ref "U4") (pin "2") (pinfunction "GND_2") (pintype "unspecified"))
      (node (ref "U5") (pin "2") (pinfunction "GND_2") (pintype "unspecified"))
    )
    (net (code "32") (name "Net-(BOOT-Pad1)") (class "Default")
      (node (ref "BOOT") (pin "1") (pinfunction "1_1") (pintype "input"))
      (node (ref "R24") (pin "1") (pinfunction "1_1") (pintype "input"))
    )
    (net (code "33") (name "Net-(C1-CC1)") (class "Default")
      (node (ref "C1") (pin "4") (pinfunction "CC1_4") (pintype "unspecified"))
      (node (ref "R19") (pin "1") (pinfunction "1_1") (pintype "input"))
    )
    (net (code "34") (name "Net-(C1-CC2)") (class "Default")
      (node (ref "C1") (pin "10") (pinfunction "CC2_10") (pintype "unspecified"))
      (node (ref "R18") (pin "1") (pinfunction "1_1") (pintype "input"))
    )
    (net (code "35") (name "Net-(LED106-A)") (class "Default")
      (node (ref "LED106") (pin "2") (pinfunction "A_2") (pintype "input"))
      (node (ref "R52") (pin "1") (pinfunction "1_1") (pintype "input"))
    )
    (net (code "36") (name "Net-(LED106-C)") (class "Default")
      (node (ref "LED106") (pin "1") (pinfunction "C_1") (pintype "input"))
      (node (ref "U2") (pin "4") (pinfunction "P3.2/TXD1_/INT0/VBUS1_4") (pintype "unspecified"))
    )
    (net (code "37") (name "Net-(U2-RST{slash}T2EX_{slash}CAP2_)") (class "Default")
      (node (ref "C6") (pin "1") (pinfunction "1_1") (pintype "unspecified"))
      (node (ref "R23") (pin "1") (pinfunction "1_1") (pintype "input"))
      (node (ref "RST") (pin "1") (pinfunction "1_1") (pintype "input"))
      (node (ref "U2") (pin "7") (pinfunction "RST/T2EX_/CAP2__7") (pintype "unspecified"))
    )
    (net (code "38") (name "Net-(U3-{slash}HOLD(IO3))") (class "Default")
      (node (ref "R57") (pin "2") (pinfunction "2_2") (pintype "input"))
      (node (ref "U3") (pin "7") (pinfunction "/HOLD(IO3)_7") (pintype "unspecified"))
    )
    (net (code "39") (name "Net-(U3-{slash}WP(IO2))") (class "Default")
      (node (ref "R56") (pin "2") (pinfunction "2_2") (pintype "input"))
      (node (ref "U3") (pin "3") (pinfunction "/WP(IO2)_3") (pintype "unspecified"))
    )
    (net (code "40") (name "SPI_CS") (class "Default")
      (node (ref "R55") (pin "2") (pinfunction "2_2") (pintype "input"))
      (node (ref "U1") (pin "17") (pinfunction "GPIO4/SPI_SS_17") (pintype "unspecified"))
      (node (ref "U2") (pin "3") (pinfunction "P1.4/T2_/CAP1_/SCS_3") (pintype "unspecified"))
      (node (ref "U3") (pin "1") (pinfunction "/CS_1") (pintype "unspecified"))
    )
    (net (code "41") (name "SPI_MISO") (class "Default")
      (node (ref "U1") (pin "18") (pinfunction "GPIO5/SPI_SI_18") (pintype "unspecified"))
      (node (ref "U2") (pin "5") (pinfunction "P1.6/MISO/RXD1/TIN4_5") (pintype "unspecified"))
      (node (ref "U3") (pin "2") (pinfunction "DO(IO1)_2") (pintype "unspecified"))
    )
    (net (code "42") (name "SPI_MOSI") (class "Default")
      (node (ref "U1") (pin "19") (pinfunction "GPIO6/SPI_SO_19") (pintype "unspecified"))
      (node (ref "U2") (pin "2") (pinfunction "P1.5/MOSI/PWM1/TIN3_2") (pintype "unspecified"))
      (node (ref "U3") (pin "5") (pinfunction "DI(IO0)_5") (pintype "unspecified"))
    )
    (net (code "43") (name "SPI_SCK") (class "Default")
      (node (ref "U1") (pin "16") (pinfunction "GPIO3/SPI_CLK_16") (pintype "unspecified"))
      (node (ref "U2") (pin "6") (pinfunction "P1.7/SCK/TXD1/TIN5_6") (pintype "unspecified"))
      (node (ref "U3") (pin "6") (pinfunction "CLK_6") (pintype "unspecified"))
    )
    (net (code "44") (name "USB_D+") (class "Default")
      (node (ref "C1") (pin "6") (pinfunction "DP1_6") (pintype "unspecified"))
      (node (ref "C1") (pin "8") (pinfunction "DP2_8") (pintype "unspecified"))
      (node (ref "R24") (pin "2") (pinfunction "2_2") (pintype "input"))
      (node (ref "U2") (pin "14") (pinfunction "P3.6/UDP_14") (pintype "unspecified"))
    )
    (net (code "45") (name "USB_D-") (class "Default")
      (node (ref "C1") (pin "5") (pinfunction "DN2_5") (pintype "unspecified"))
      (node (ref "C1") (pin "7") (pinfunction "DN1_7") (pintype "unspecified"))
      (node (ref "U2") (pin "15") (pinfunction "P3.7/UDM_15") (pintype "unspecified"))
    )
    (net (code "46") (name "VBUS") (class "Default")
      (node (ref "C1") (pin "11") (pinfunction "VBUS_11") (pintype "unspecified"))
      (node (ref "C1") (pin "2") (pinfunction "VBUS_2") (pintype "unspecified"))
      (node (ref "F1") (pin "1") (pinfunction "1_1") (pintype "input"))
    )
    (net (code "47") (name "VIN") (class "Default")
      (node (ref "C17") (pin "2") (pinfunction "2_2") (pintype "unspecified"))
      (node (ref "F1") (pin "2") (pinfunction "2_2") (pintype "input"))
      (node (ref "U4") (pin "1") (pinfunction "IN_1") (pintype "unspecified"))
      (node (ref "U4") (pin "3") (pinfunction "EN_3") (pintype "unspecified"))
    )
    (net (code "48") (name "unconnected-(BOOT-Pad2)") (class "Default")
      (node (ref "BOOT") (pin "2") (pinfunction "2_2") (pintype "input+no_connect"))
    )
    (net (code "49") (name "unconnected-(BOOT-Pad4)") (class "Default")
      (node (ref "BOOT") (pin "4") (pinfunction "4_4") (pintype "input+no_connect"))
    )
    (net (code "50") (name "unconnected-(BTN1-Pad2)") (class "Default")
      (node (ref "BTN1") (pin "2") (pinfunction "2_2") (pintype "input+no_connect"))
    )
    (net (code "51") (name "unconnected-(BTN1-Pad4)") (class "Default")
      (node (ref "BTN1") (pin "4") (pinfunction "4_4") (pintype "input+no_connect"))
    )
    (net (code "52") (name "unconnected-(BTN2-Pad2)") (class "Default")
      (node (ref "BTN2") (pin "2") (pinfunction "2_2") (pintype "input+no_connect"))
    )
    (net (code "53") (name "unconnected-(BTN2-Pad4)") (class "Default")
      (node (ref "BTN2") (pin "4") (pinfunction "4_4") (pintype "input+no_connect"))
    )
    (net (code "54") (name "unconnected-(BTN3-Pad2)") (class "Default")
      (node (ref "BTN3") (pin "2") (pinfunction "2_2") (pintype "input+no_connect"))
    )
    (net (code "55") (name "unconnected-(BTN3-Pad4)") (class "Default")
      (node (ref "BTN3") (pin "4") (pinfunction "4_4") (pintype "input+no_connect"))
    )
    (net (code "56") (name "unconnected-(BTN4-Pad2)") (class "Default")
      (node (ref "BTN4") (pin "2") (pinfunction "2_2") (pintype "input+no_connect"))
    )
    (net (code "57") (name "unconnected-(BTN4-Pad4)") (class "Default")
      (node (ref "BTN4") (pin "4") (pinfunction "4_4") (pintype "input+no_connect"))
    )
    (net (code "58") (name "unconnected-(C1-SBU1-Pad9)") (class "Default")
      (node (ref "C1") (pin "9") (pinfunction "SBU1_9") (pintype "unspecified+no_connect"))
    )
    (net (code "59") (name "unconnected-(C1-SBU2-Pad3)") (class "Default")
      (node (ref "C1") (pin "3") (pinfunction "SBU2_3") (pintype "unspecified+no_connect"))
    )
    (net (code "60") (name "unconnected-(RST-Pad2)") (class "Default")
      (node (ref "RST") (pin "2") (pinfunction "2_2") (pintype "input+no_connect"))
    )
    (net (code "61") (name "unconnected-(RST-Pad4)") (class "Default")
      (node (ref "RST") (pin "4") (pinfunction "4_4") (pintype "input+no_connect"))
    )
    (net (code "62") (name "unconnected-(U2-P1.1{slash}T2EX{slash}CAP2{slash}TIN1-Pad11)") (class "Default")
      (node (ref "U2") (pin "11") (pinfunction "P1.1/T2EX/CAP2/TIN1_11") (pintype "unspecified+no_connect"))
    )
    (net (code "63") (name "unconnected-(U2-P3.0{slash}PWM1_{slash}RXD-Pad10)") (class "Default")
      (node (ref "U2") (pin "10") (pinfunction "P3.0/PWM1_/RXD_10") (pintype "unspecified+no_connect"))
    )
    (net (code "64") (name "unconnected-(U2-P3.1{slash}PWM2_{slash}TXD-Pad9)") (class "Default")
      (node (ref "U2") (pin "9") (pinfunction "P3.1/PWM2_/TXD_9") (pintype "unspecified+no_connect"))
    )
    (net (code "65") (name "unconnected-(U2-P3.4{slash}PWM2{slash}RXD1_{slash}T0-Pad13)") (class "Default")
      (node (ref "U2") (pin "13") (pinfunction "P3.4/PWM2/RXD1_/T0_13") (pintype "unspecified+no_connect"))
    )
    (net (code "66") (name "unconnected-(U4-NC-Pad4)") (class "Default")
      (node (ref "U4") (pin "4") (pinfunction "NC_4") (pintype "unspecified+no_connect"))
    )
    (net (code "67") (name "unconnected-(U5-NC-Pad4)") (class "Default")
      (node (ref "U5") (pin "4") (pinfunction "NC_4") (pintype "unspecified+no_connect"))
    )
  )
)
